# expansionboard.net
KiCad netlist of a schematic drawn in EAGLE
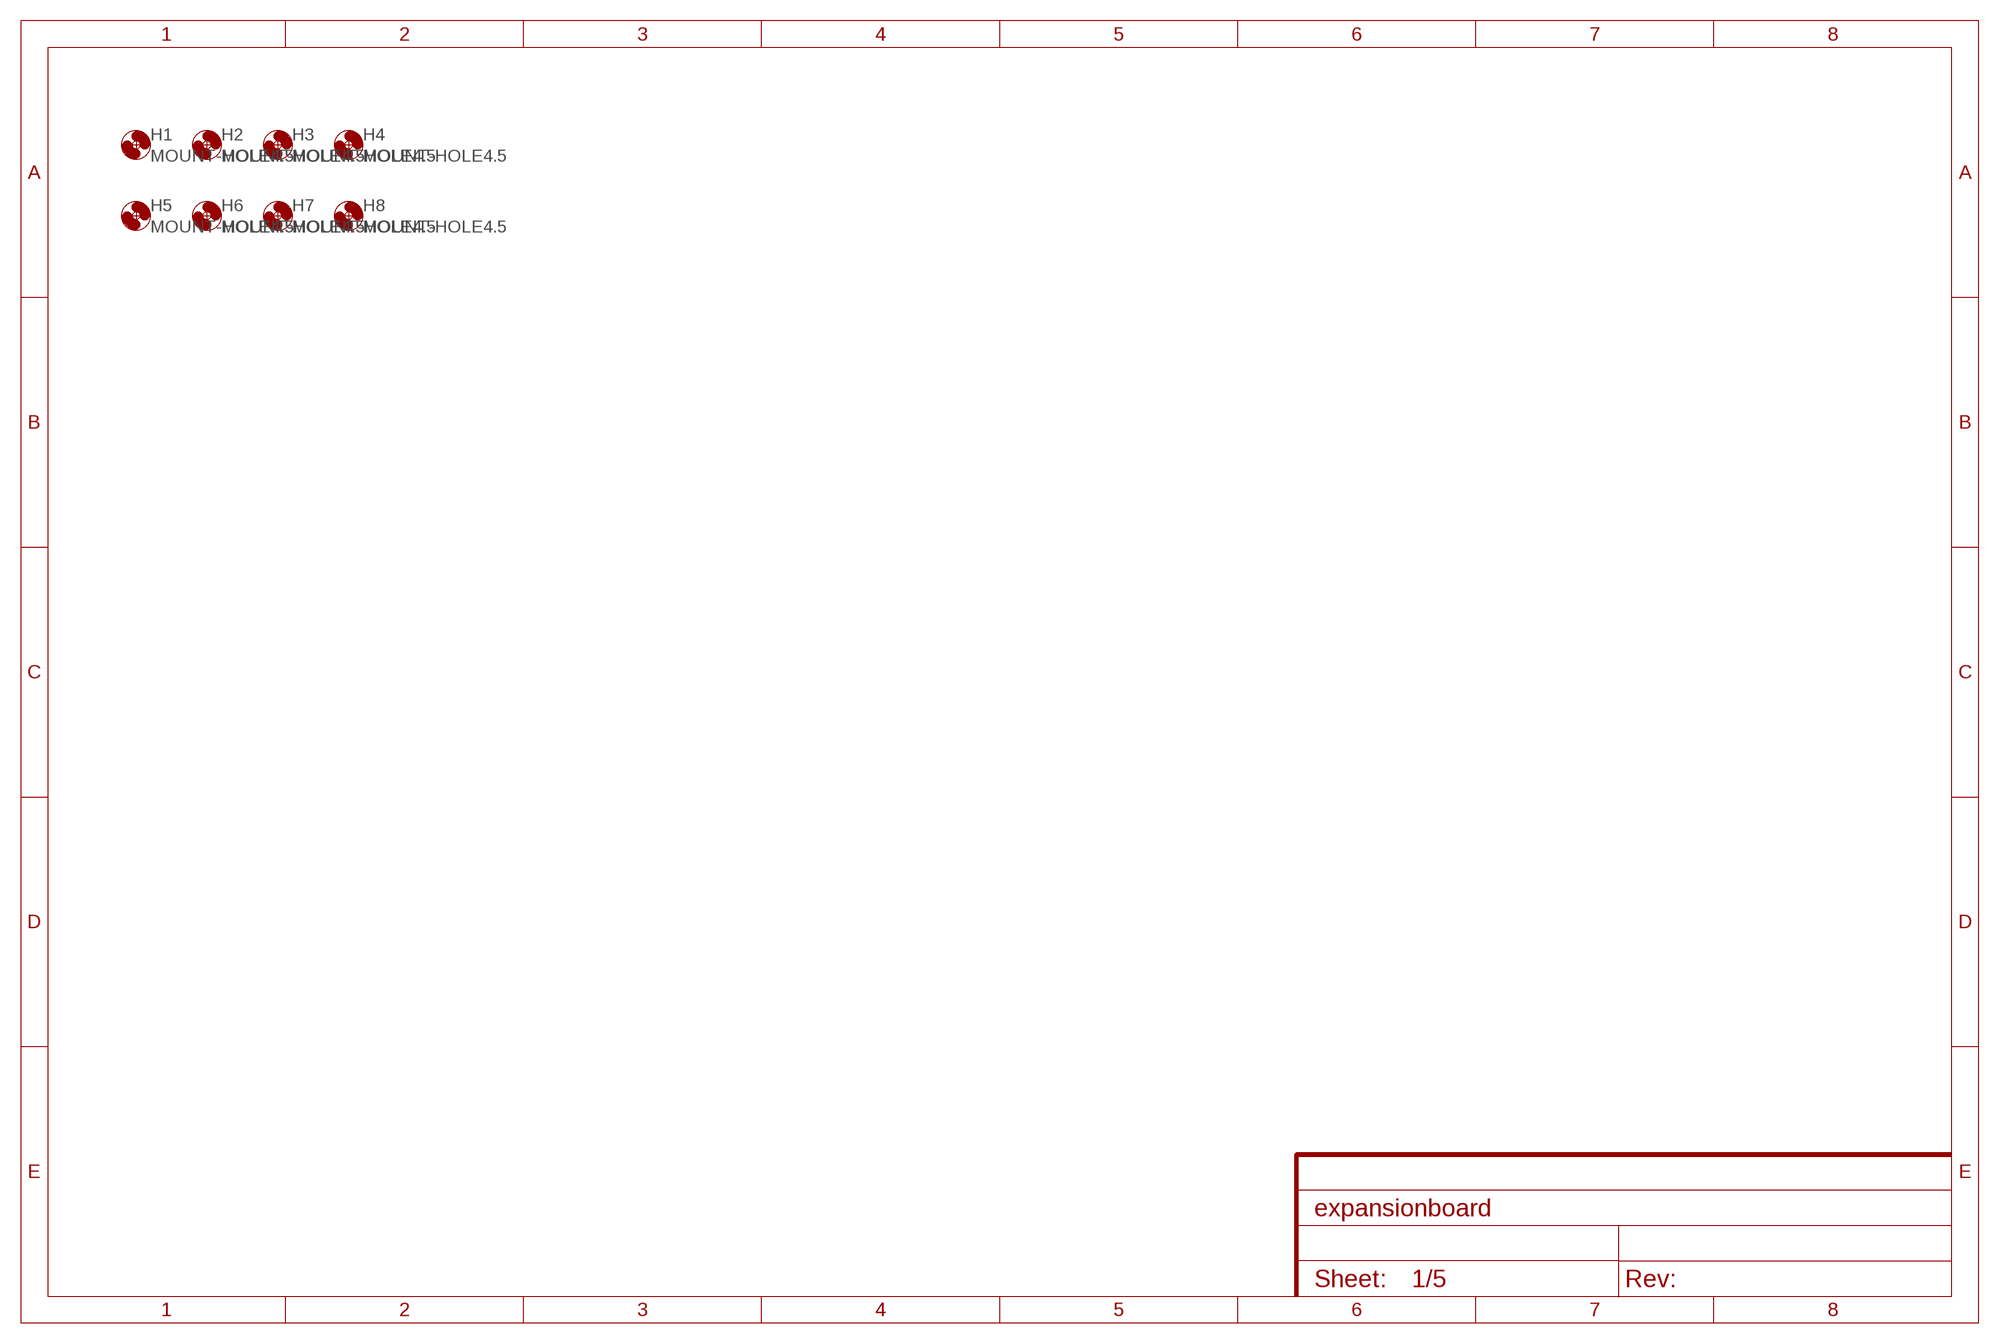
[diagram p0: schematic, sheet 1]
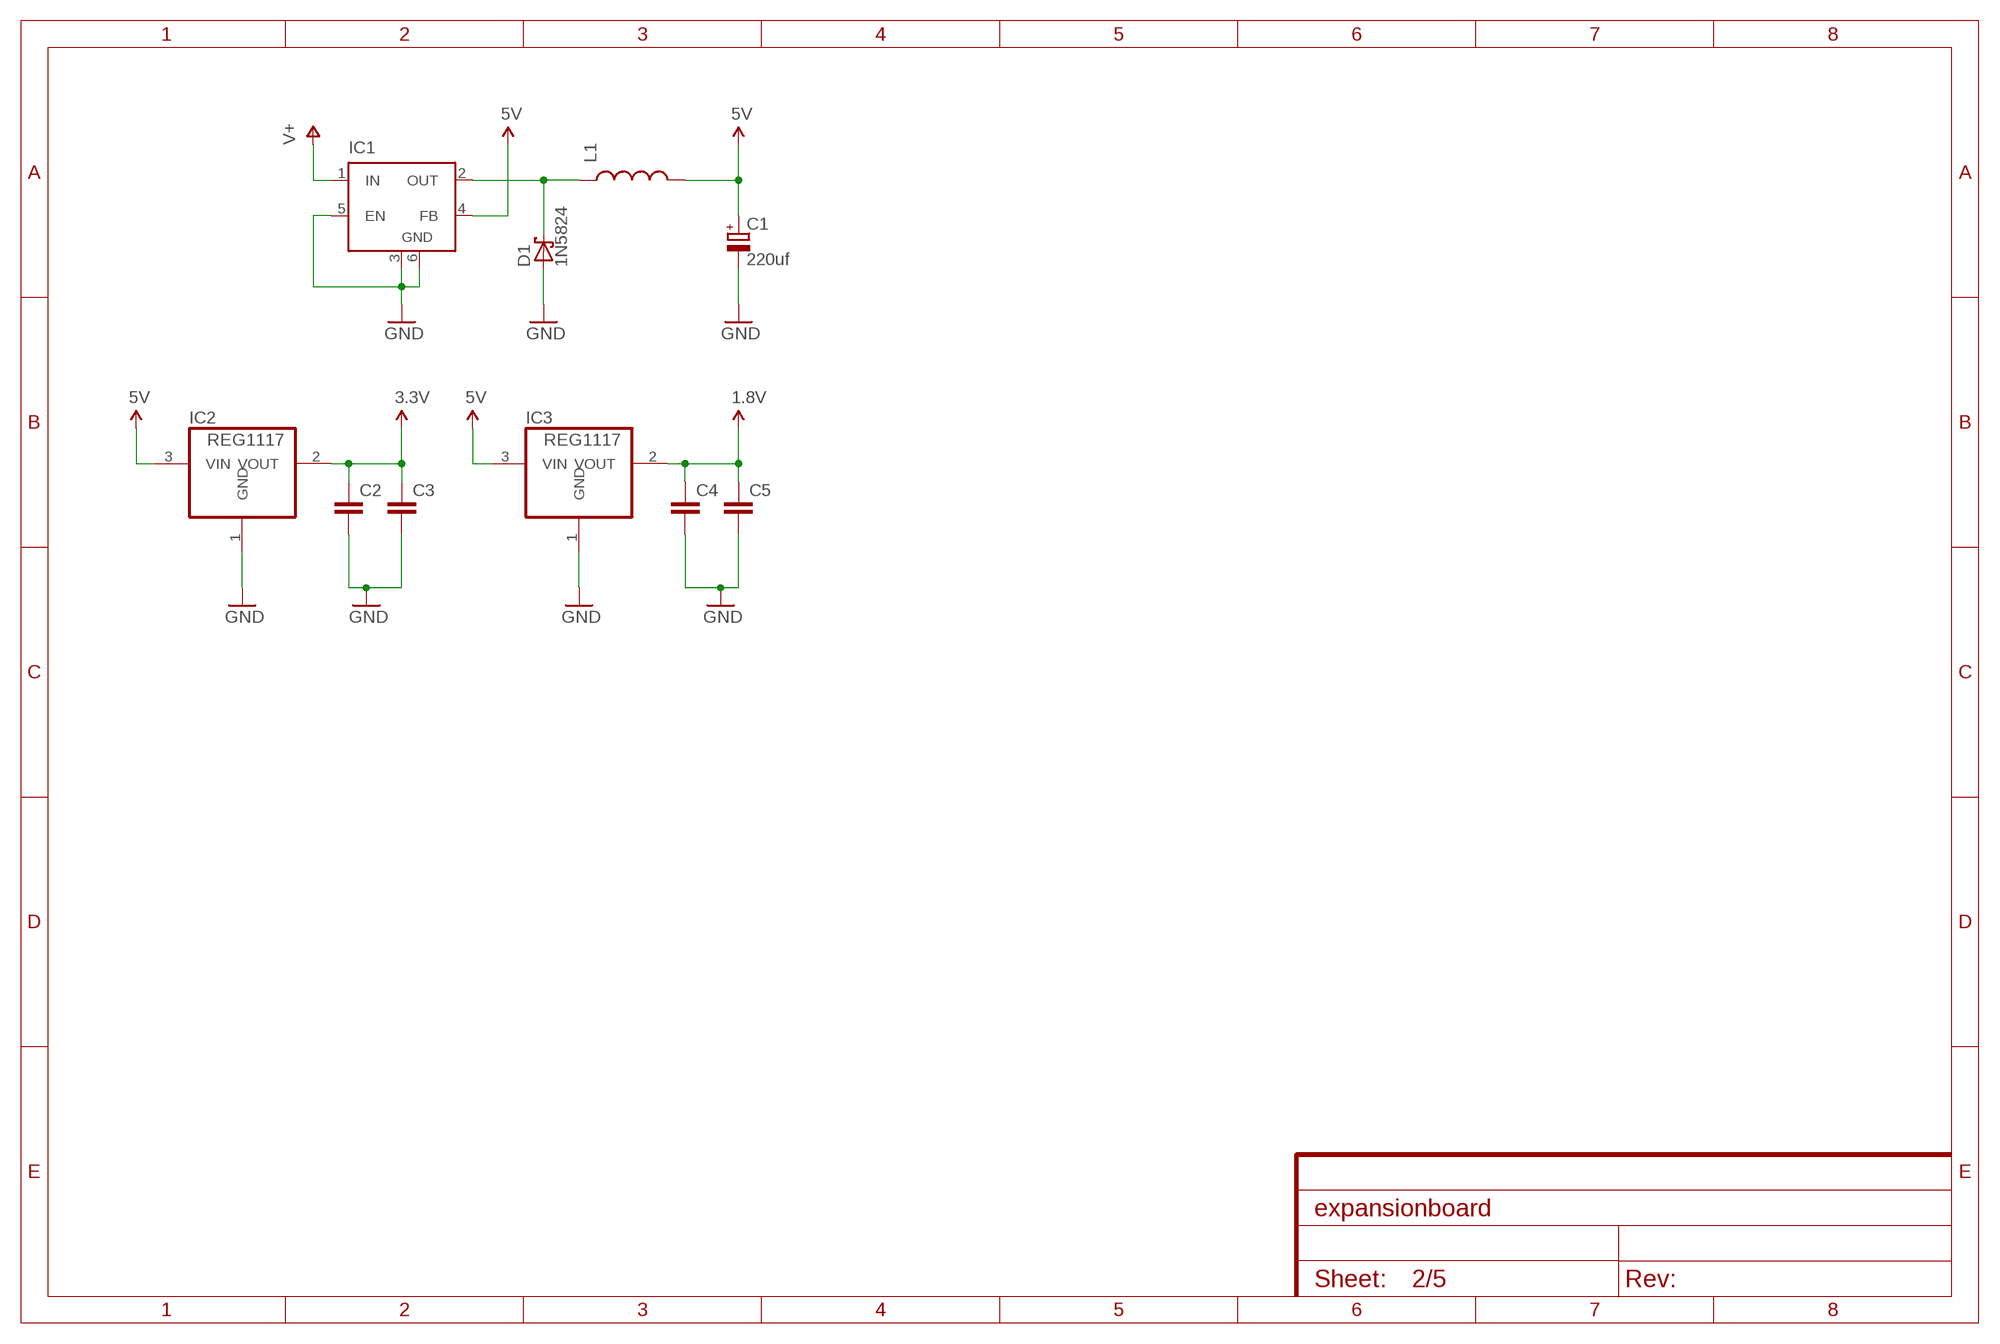
[diagram p1: schematic, sheet 2]
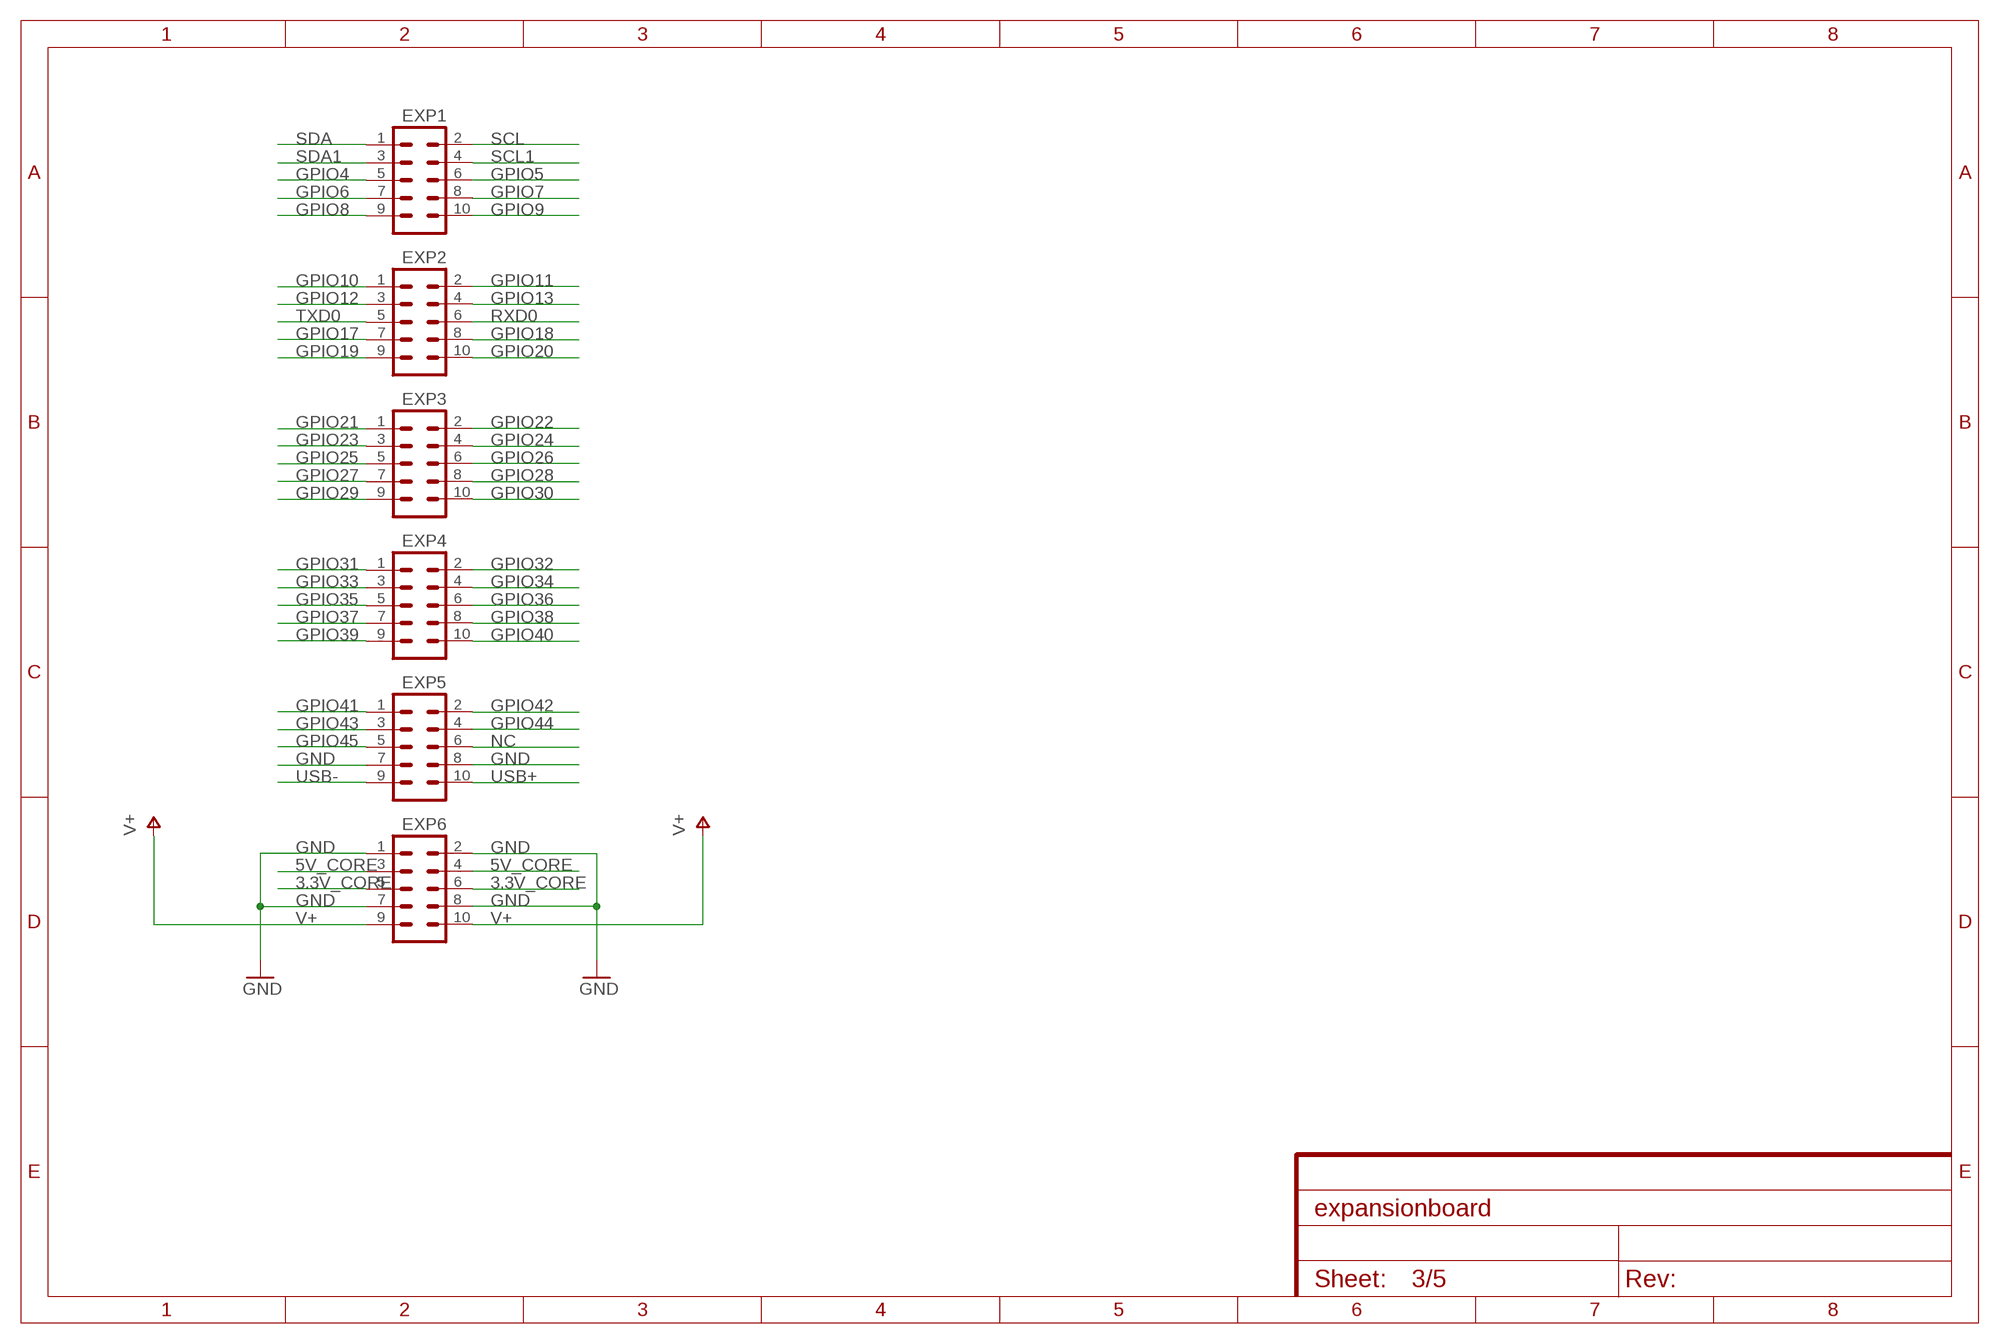
[diagram p2: schematic, sheet 3]
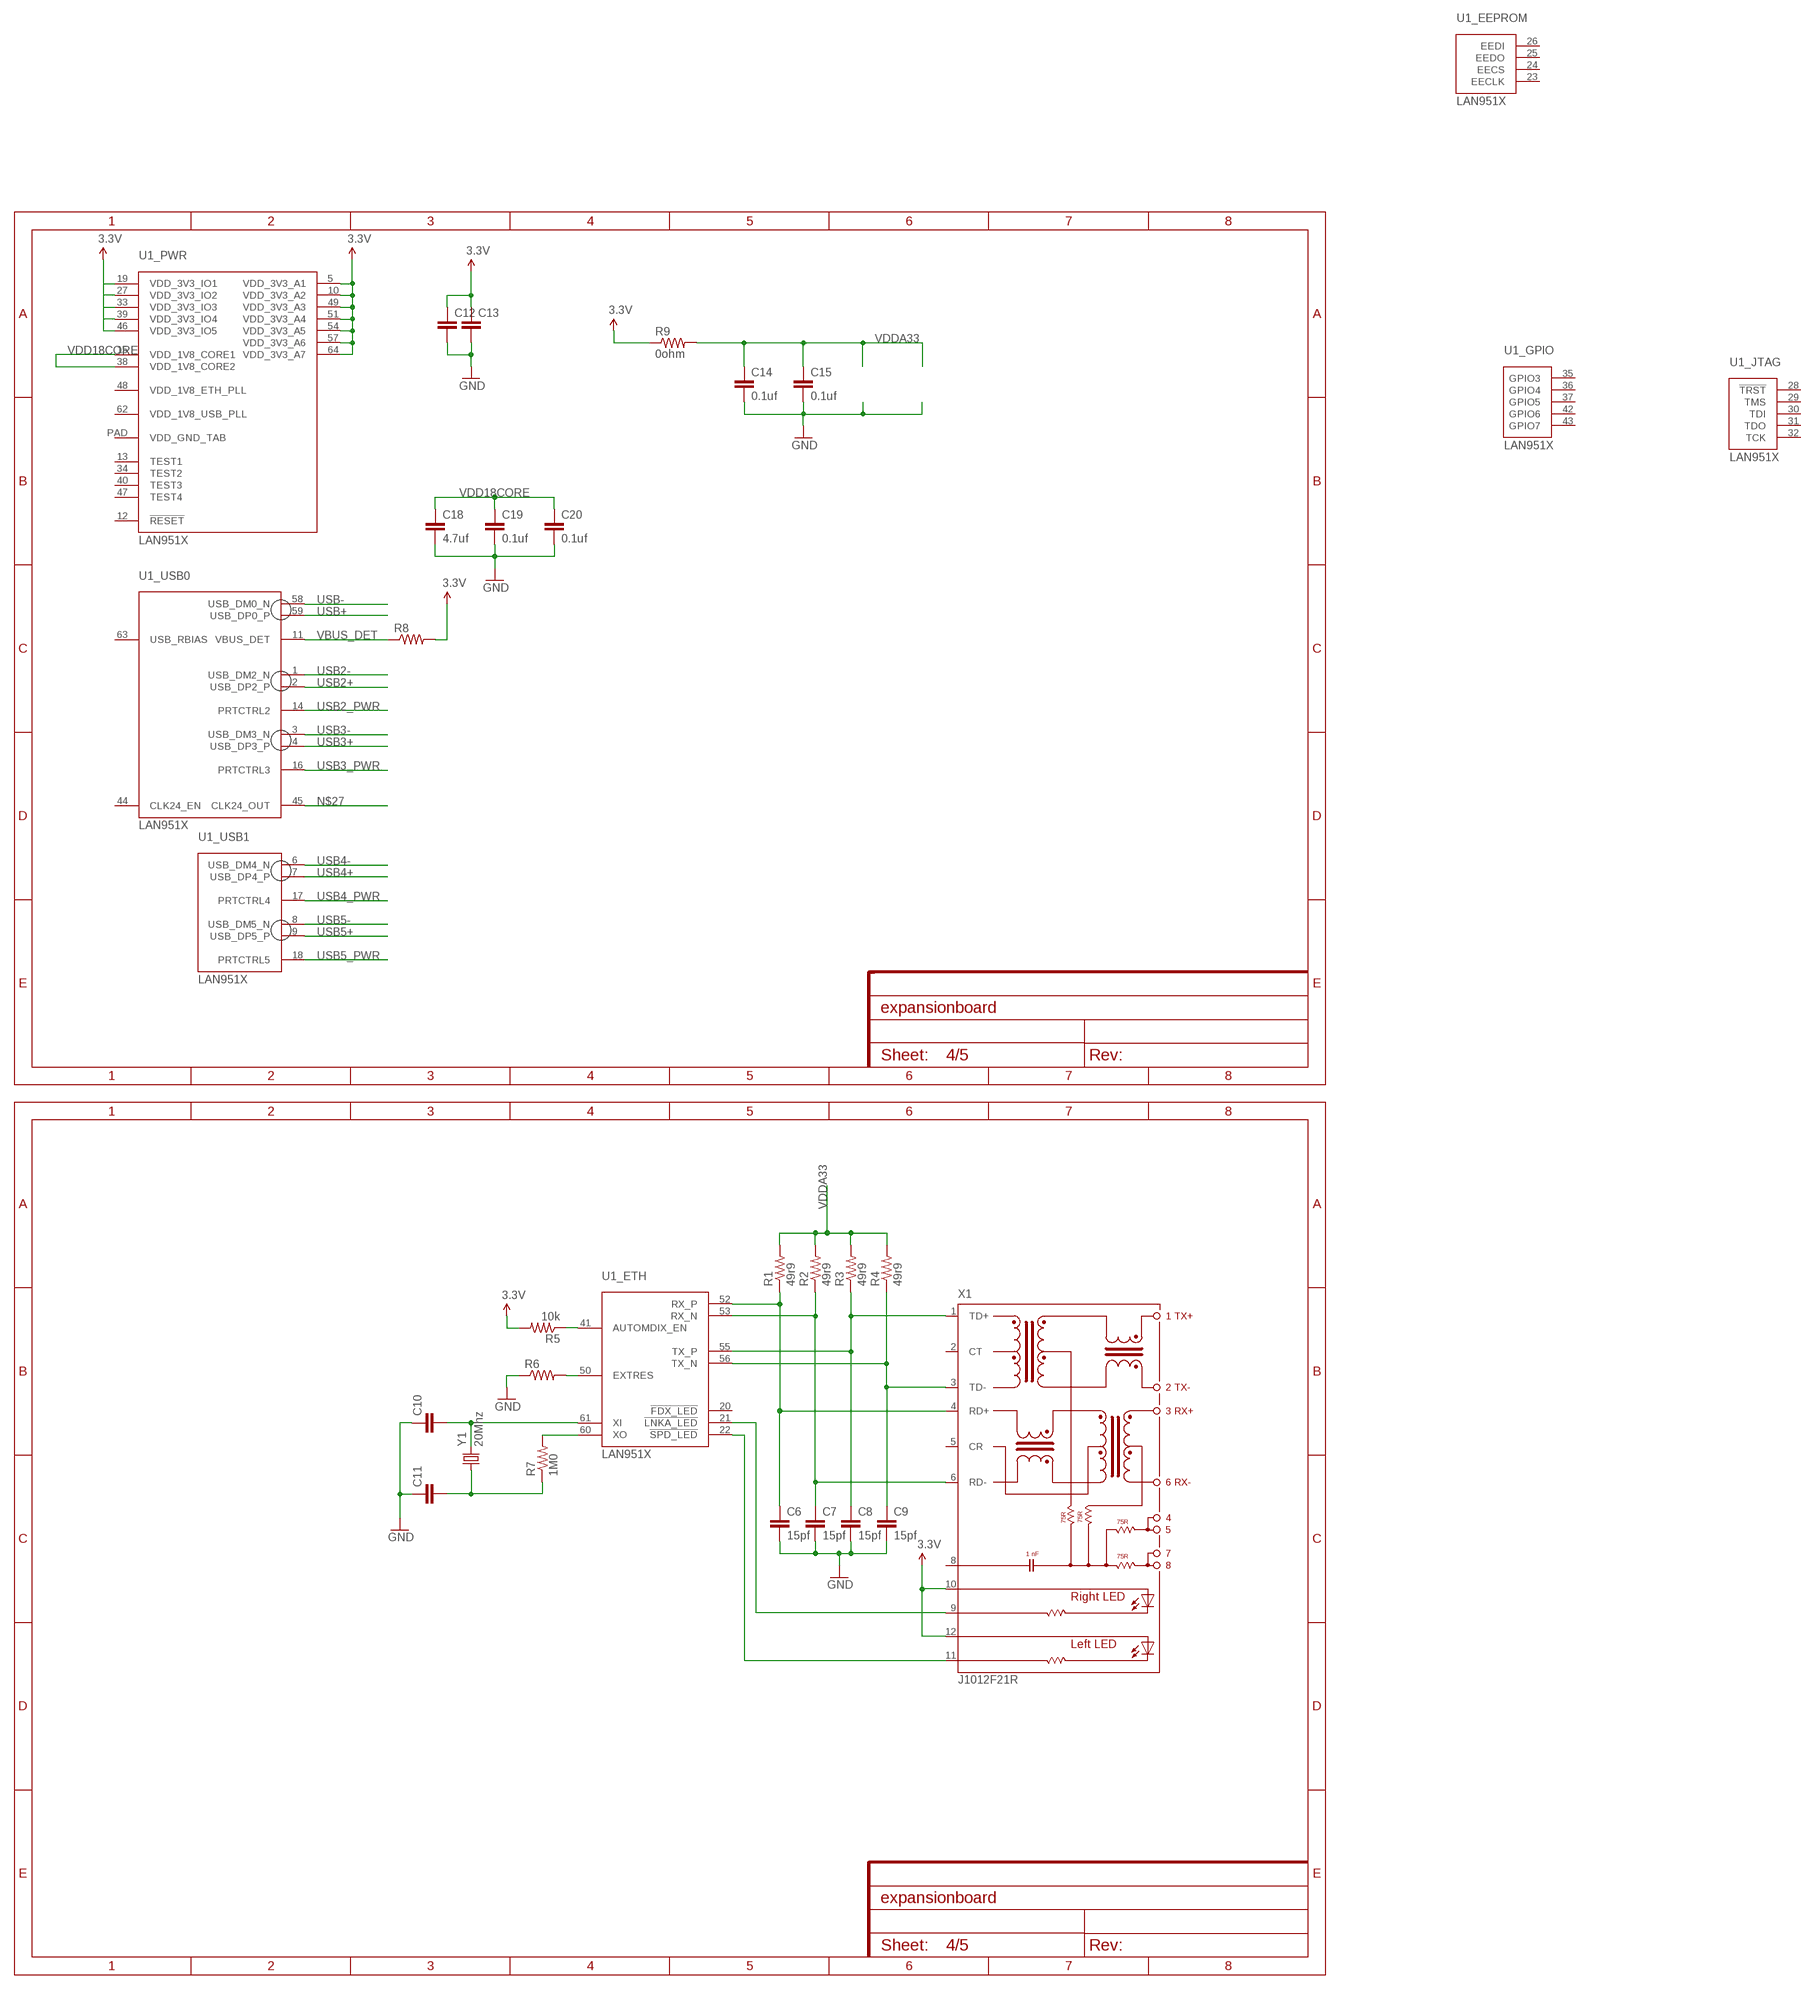
[diagram p3: schematic, sheet 4]
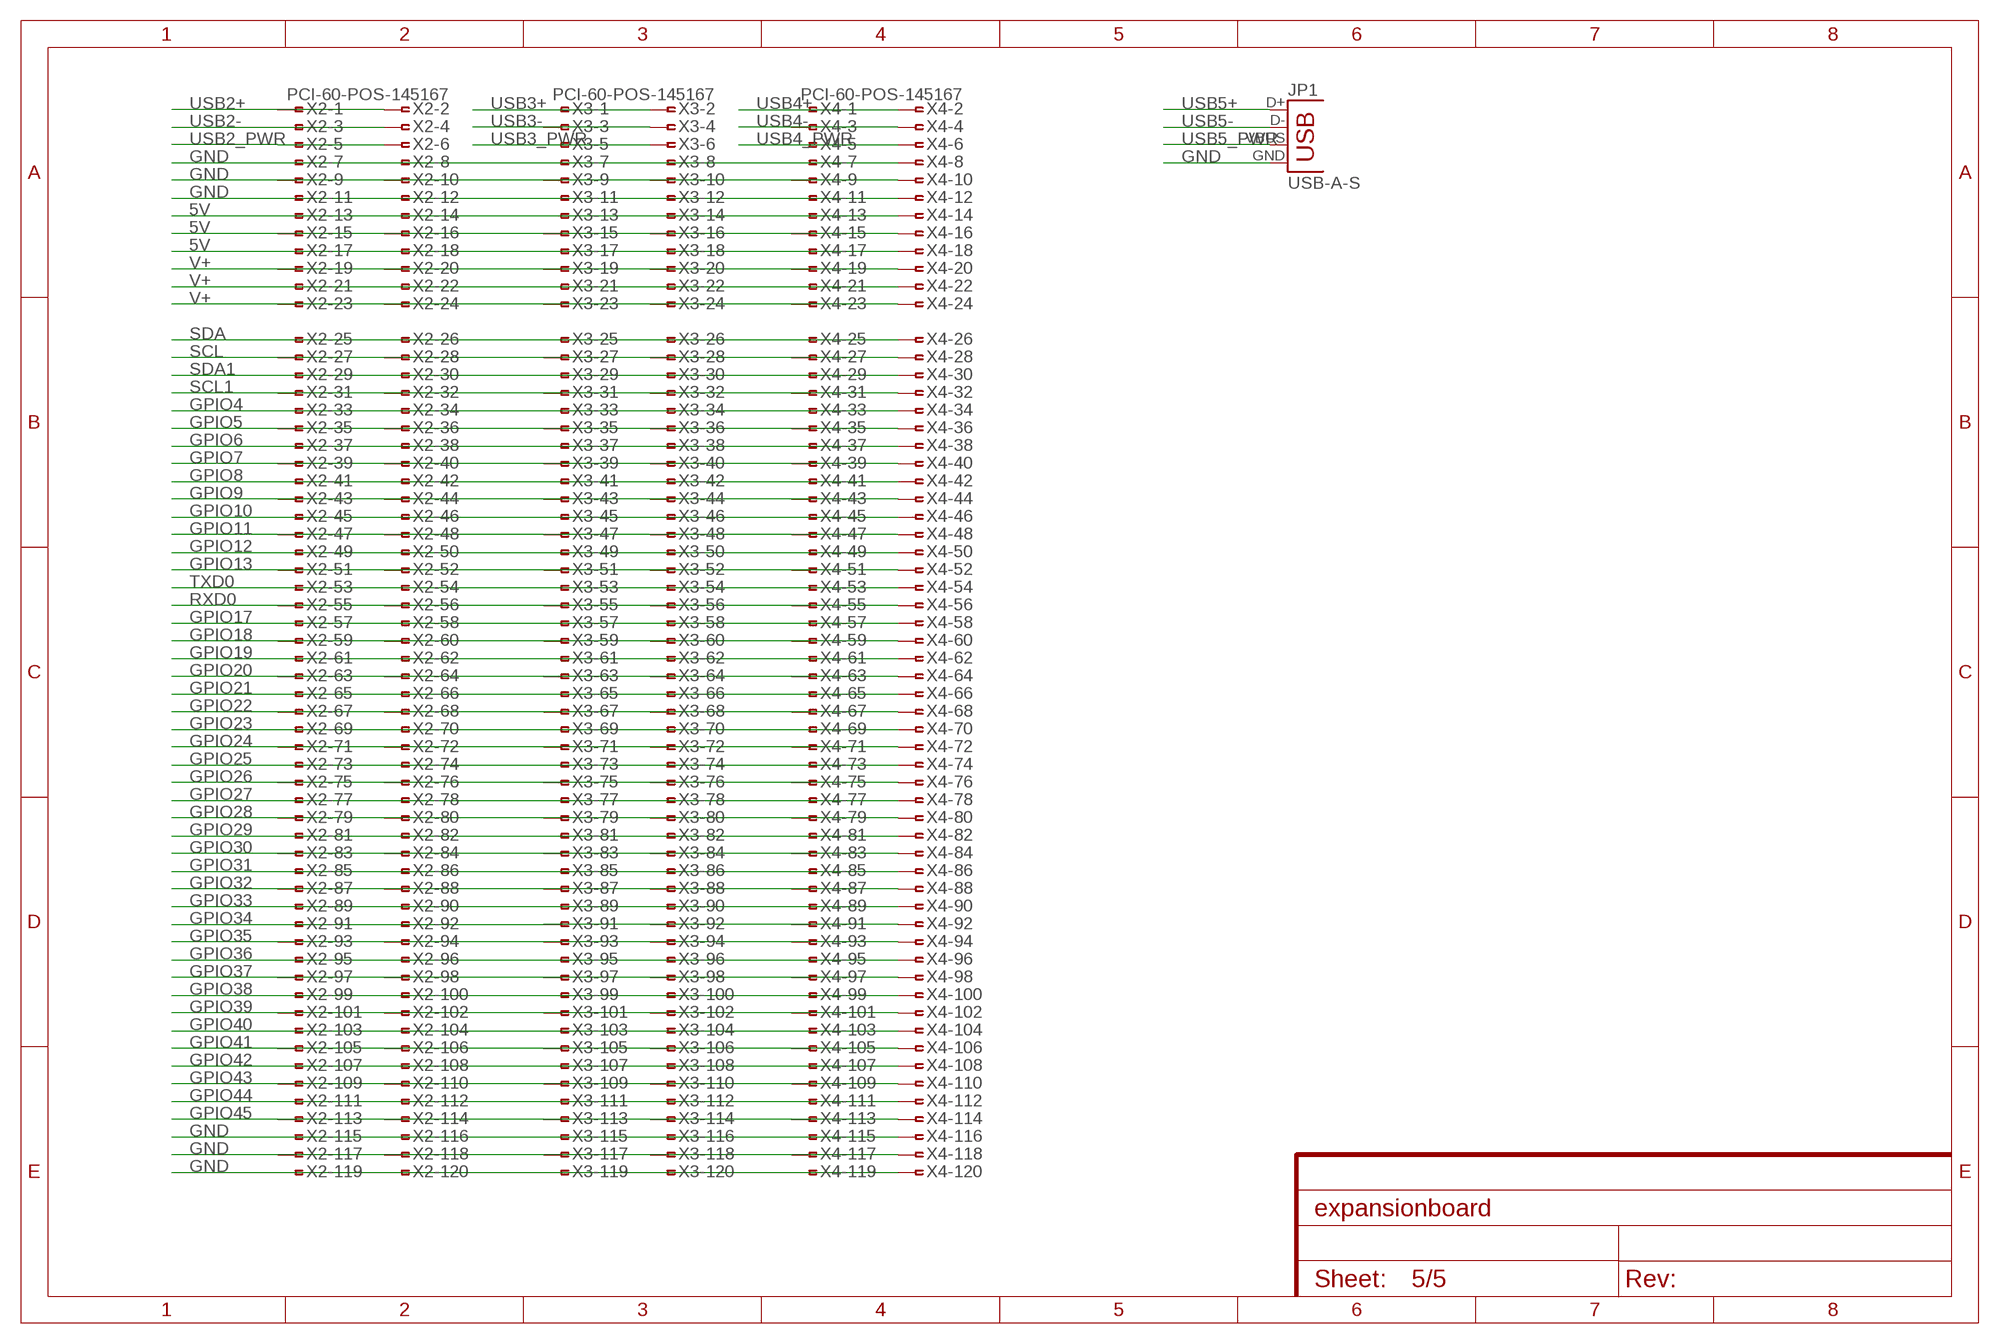
[diagram p4: schematic, sheet 5]

(export (version "E")
  (design (tool "Eeschema 10.0.6"))
  (components
    (comp (ref "C1")
      (value "220uf")
      (footprint "eagle-import:E2,5-6")
      (libsource (lib "eagle-import") (part "CPOL-EUE2.5-6"))
    )
    (comp (ref "C2")
      (value "CAP1206")
      (footprint "eagle-import:1206")
      (libsource (lib "eagle-import") (part "CAP1206"))
    )
    (comp (ref "C3")
      (value "CAP1206")
      (footprint "eagle-import:1206")
      (libsource (lib "eagle-import") (part "CAP1206"))
    )
    (comp (ref "C4")
      (value "CAP1206")
      (footprint "eagle-import:1206")
      (libsource (lib "eagle-import") (part "CAP1206"))
    )
    (comp (ref "C5")
      (value "CAP1206")
      (footprint "eagle-import:1206")
      (libsource (lib "eagle-import") (part "CAP1206"))
    )
    (comp (ref "D1")
      (value "1N5824")
      (footprint "eagle-import:DO41-7.6")
      (libsource (lib "eagle-import") (part "1N5817-B"))
    )
    (comp (ref "IC1")
      (value "LM2596S")
      (footprint "eagle-import:TO263-5")
      (libsource (lib "eagle-import") (part "LM2596S"))
    )
    (comp (ref "IC2")
      (value "REG1117")
      (footprint "eagle-import:SOT223")
      (libsource (lib "eagle-import") (part "REG1117"))
    )
    (comp (ref "IC3")
      (value "REG1117")
      (footprint "eagle-import:SOT223")
      (libsource (lib "eagle-import") (part "REG1117"))
    )
    (comp (ref "L1")
      (value "INDUCTORSRU1038")
      (footprint "eagle-import:SRU1038")
      (libsource (lib "eagle-import") (part "INDUCTORSRU1038"))
    )
    (comp (ref "EXP1")
      (value "M05X2SHD_LOCK")
      (footprint "eagle-import:2X5-SHROUDED_LOCK")
      (libsource (lib "eagle-import") (part "M05X2SHD_LOCK"))
    )
    (comp (ref "EXP2")
      (value "M05X2SHD_LOCK")
      (footprint "eagle-import:2X5-SHROUDED_LOCK")
      (libsource (lib "eagle-import") (part "M05X2SHD_LOCK"))
    )
    (comp (ref "EXP3")
      (value "M05X2SHD_LOCK")
      (footprint "eagle-import:2X5-SHROUDED_LOCK")
      (libsource (lib "eagle-import") (part "M05X2SHD_LOCK"))
    )
    (comp (ref "EXP4")
      (value "M05X2SHD_LOCK")
      (footprint "eagle-import:2X5-SHROUDED_LOCK")
      (libsource (lib "eagle-import") (part "M05X2SHD_LOCK"))
    )
    (comp (ref "EXP5")
      (value "M05X2SHD_LOCK")
      (footprint "eagle-import:2X5-SHROUDED_LOCK")
      (libsource (lib "eagle-import") (part "M05X2SHD_LOCK"))
    )
    (comp (ref "EXP6")
      (value "M05X2SHD_LOCK")
      (footprint "eagle-import:2X5-SHROUDED_LOCK")
      (libsource (lib "eagle-import") (part "M05X2SHD_LOCK"))
    )
    (comp (ref "JP1")
      (value "USB-A-S")
      (footprint "eagle-import:USB-A-S")
      (libsource (lib "eagle-import") (part "USB-A-S"))
    )
    (comp (ref "X2")
      (value "PCI-60-POS-145167")
      (footprint "eagle-import:145167-2")
      (libsource (lib "eagle-import") (part "PCI-60-POS-145167"))
    )
    (comp (ref "X3")
      (value "PCI-60-POS-145167")
      (footprint "eagle-import:145167-2")
      (libsource (lib "eagle-import") (part "PCI-60-POS-145167"))
    )
    (comp (ref "X4")
      (value "PCI-60-POS-145167")
      (footprint "eagle-import:145167-2")
      (libsource (lib "eagle-import") (part "PCI-60-POS-145167"))
    )
    (comp (ref "C6")
      (value "15pf")
      (footprint "eagle-import:CAP-PTH-SMALLEZ")
      (libsource (lib "eagle-import") (part "CAPEZ"))
    )
    (comp (ref "C7")
      (value "15pf")
      (footprint "eagle-import:CAP-PTH-SMALLEZ")
      (libsource (lib "eagle-import") (part "CAPEZ"))
    )
    (comp (ref "C8")
      (value "15pf")
      (footprint "eagle-import:CAP-PTH-SMALLEZ")
      (libsource (lib "eagle-import") (part "CAPEZ"))
    )
    (comp (ref "C9")
      (value "15pf")
      (footprint "eagle-import:CAP-PTH-SMALLEZ")
      (libsource (lib "eagle-import") (part "CAPEZ"))
    )
    (comp (ref "C10")
      (value "CAPEZ")
      (footprint "eagle-import:CAP-PTH-SMALLEZ")
      (libsource (lib "eagle-import") (part "CAPEZ"))
    )
    (comp (ref "C11")
      (value "CAPEZ")
      (footprint "eagle-import:CAP-PTH-SMALLEZ")
      (libsource (lib "eagle-import") (part "CAPEZ"))
    )
    (comp (ref "C12")
      (value "CAPEZ")
      (footprint "eagle-import:CAP-PTH-SMALLEZ")
      (libsource (lib "eagle-import") (part "CAPEZ"))
    )
    (comp (ref "C13")
      (value "CAPEZ")
      (footprint "eagle-import:CAP-PTH-SMALLEZ")
      (libsource (lib "eagle-import") (part "CAPEZ"))
    )
    (comp (ref "C14")
      (value "0.1uf")
      (footprint "eagle-import:1206")
      (libsource (lib "eagle-import") (part "CAP1206"))
    )
    (comp (ref "C15")
      (value "0.1uf")
      (footprint "eagle-import:1206")
      (libsource (lib "eagle-import") (part "CAP1206"))
    )
    (comp (ref "C18")
      (value "4.7uf")
      (footprint "eagle-import:1206")
      (libsource (lib "eagle-import") (part "CAP1206"))
    )
    (comp (ref "C19")
      (value "0.1uf")
      (footprint "eagle-import:1206")
      (libsource (lib "eagle-import") (part "CAP1206"))
    )
    (comp (ref "C20")
      (value "0.1uf")
      (footprint "eagle-import:1206")
      (libsource (lib "eagle-import") (part "CAP1206"))
    )
    (comp (ref "R1")
      (value "49r9")
      (footprint "eagle-import:AXIAL-0.3EZ")
      (libsource (lib "eagle-import") (part "RESISTOREZ"))
    )
    (comp (ref "R2")
      (value "49r9")
      (footprint "eagle-import:AXIAL-0.3EZ")
      (libsource (lib "eagle-import") (part "RESISTOREZ"))
    )
    (comp (ref "R3")
      (value "49r9")
      (footprint "eagle-import:AXIAL-0.3EZ")
      (libsource (lib "eagle-import") (part "RESISTOREZ"))
    )
    (comp (ref "R4")
      (value "49r9")
      (footprint "eagle-import:AXIAL-0.3EZ")
      (libsource (lib "eagle-import") (part "RESISTOREZ"))
    )
    (comp (ref "R5")
      (value "10k")
      (footprint "eagle-import:AXIAL-0.3EZ")
      (libsource (lib "eagle-import") (part "RESISTOREZ"))
    )
    (comp (ref "R6")
      (value "RESISTOREZ")
      (footprint "eagle-import:AXIAL-0.3EZ")
      (libsource (lib "eagle-import") (part "RESISTOREZ"))
    )
    (comp (ref "R7")
      (value "1M0")
      (footprint "eagle-import:AXIAL-0.3EZ")
      (libsource (lib "eagle-import") (part "RESISTOREZ"))
    )
    (comp (ref "R8")
      (value "RESISTOR1206")
      (footprint "eagle-import:1206")
      (libsource (lib "eagle-import") (part "RESISTOR1206"))
    )
    (comp (ref "R9")
      (value "0ohm")
      (footprint "eagle-import:1206")
      (libsource (lib "eagle-import") (part "RESISTOR1206"))
    )
    (comp (ref "U1")
      (value "LAN951X")
      (footprint "eagle-import:QFN-64")
      (libsource (lib "eagle-import") (part "LAN951X"))
    )
    (comp (ref "X1")
      (value "J1012F21R")
      (footprint "eagle-import:J1")
      (libsource (lib "eagle-import") (part "J1012F21R"))
    )
    (comp (ref "Y1")
      (value "20Mhz")
      (footprint "eagle-import:HC49US")
      (libsource (lib "eagle-import") (part "CRYSTALHC49US"))
    )
    (comp (ref "H1")
      (value "MOUNT-HOLE4.5")
      (footprint "eagle-import:4,5")
      (libsource (lib "eagle-import") (part "MOUNT-HOLE4.5"))
    )
    (comp (ref "H2")
      (value "MOUNT-HOLE4.5")
      (footprint "eagle-import:4,5")
      (libsource (lib "eagle-import") (part "MOUNT-HOLE4.5"))
    )
    (comp (ref "H3")
      (value "MOUNT-HOLE4.5")
      (footprint "eagle-import:4,5")
      (libsource (lib "eagle-import") (part "MOUNT-HOLE4.5"))
    )
    (comp (ref "H4")
      (value "MOUNT-HOLE4.5")
      (footprint "eagle-import:4,5")
      (libsource (lib "eagle-import") (part "MOUNT-HOLE4.5"))
    )
    (comp (ref "H5")
      (value "MOUNT-HOLE4.5")
      (footprint "eagle-import:4,5")
      (libsource (lib "eagle-import") (part "MOUNT-HOLE4.5"))
    )
    (comp (ref "H6")
      (value "MOUNT-HOLE4.5")
      (footprint "eagle-import:4,5")
      (libsource (lib "eagle-import") (part "MOUNT-HOLE4.5"))
    )
    (comp (ref "H7")
      (value "MOUNT-HOLE4.5")
      (footprint "eagle-import:4,5")
      (libsource (lib "eagle-import") (part "MOUNT-HOLE4.5"))
    )
    (comp (ref "H8")
      (value "MOUNT-HOLE4.5")
      (footprint "eagle-import:4,5")
      (libsource (lib "eagle-import") (part "MOUNT-HOLE4.5"))
    )
  )
  (nets
    (net (code "1") (name "1.8V") (class "Default")
      (node (ref "C4") (pin "1") (pinfunction "1_1") (pintype "passive"))
      (node (ref "C5") (pin "1") (pinfunction "1_1") (pintype "passive"))
      (node (ref "IC3") (pin "2") (pinfunction "VOUT_2") (pintype "output"))
    )
    (net (code "2") (name "3.3V") (class "Default")
      (node (ref "C12") (pin "1") (pinfunction "1_1") (pintype "passive"))
      (node (ref "C13") (pin "1") (pinfunction "1_1") (pintype "passive"))
      (node (ref "C2") (pin "1") (pinfunction "1_1") (pintype "passive"))
      (node (ref "C3") (pin "1") (pinfunction "1_1") (pintype "passive"))
      (node (ref "IC2") (pin "2") (pinfunction "VOUT_2") (pintype "output"))
      (node (ref "R5") (pin "P$2") (pinfunction "2_P$2") (pintype "passive"))
      (node (ref "R8") (pin "2") (pinfunction "2_2") (pintype "passive"))
      (node (ref "R9") (pin "1") (pinfunction "1_1") (pintype "passive"))
      (node (ref "U1") (pin "10") (pinfunction "VDD_3V3_A2_10") (pintype "bidirectional"))
      (node (ref "U1") (pin "19") (pinfunction "VDD_3V3_IO1_19") (pintype "bidirectional"))
      (node (ref "U1") (pin "27") (pinfunction "VDD_3V3_IO2_27") (pintype "bidirectional"))
      (node (ref "U1") (pin "33") (pinfunction "VDD_3V3_IO3_33") (pintype "bidirectional"))
      (node (ref "U1") (pin "39") (pinfunction "VDD_3V3_IO4_39") (pintype "bidirectional"))
      (node (ref "U1") (pin "46") (pinfunction "VDD_3V3_IO5_46") (pintype "bidirectional"))
      (node (ref "U1") (pin "49") (pinfunction "VDD_3V3_A3_49") (pintype "bidirectional"))
      (node (ref "U1") (pin "5") (pinfunction "VDD_3V3_A1_5") (pintype "bidirectional"))
      (node (ref "U1") (pin "51") (pinfunction "VDD_3V3_A4_51") (pintype "bidirectional"))
      (node (ref "U1") (pin "54") (pinfunction "VDD_3V3_A5_54") (pintype "bidirectional"))
      (node (ref "U1") (pin "57") (pinfunction "VDD_3V3_A6_57") (pintype "bidirectional"))
      (node (ref "U1") (pin "64") (pinfunction "VDD_3V3_A7_64") (pintype "bidirectional"))
      (node (ref "X1") (pin "10") (pinfunction "A-R_10") (pintype "passive"))
      (node (ref "X1") (pin "12") (pinfunction "A-L_12") (pintype "passive"))
    )
    (net (code "3") (name "3.3V_CORE") (class "Default")
      (node (ref "EXP6") (pin "5") (pinfunction "5_5") (pintype "passive"))
      (node (ref "EXP6") (pin "6") (pinfunction "6_6") (pintype "passive"))
    )
    (net (code "4") (name "5V") (class "Default")
      (node (ref "C1") (pin "+") (pinfunction "+_+") (pintype "passive"))
      (node (ref "IC1") (pin "4") (pinfunction "FB_4") (pintype "input"))
      (node (ref "IC2") (pin "3") (pinfunction "VIN_3") (pintype "input"))
      (node (ref "IC3") (pin "3") (pinfunction "VIN_3") (pintype "input"))
      (node (ref "L1") (pin "2") (pinfunction "2_2") (pintype "passive"))
      (node (ref "X2") (pin "13") (pinfunction "1_13") (pintype "passive"))
      (node (ref "X2") (pin "14") (pinfunction "1_14") (pintype "passive"))
      (node (ref "X2") (pin "15") (pinfunction "1_15") (pintype "passive"))
      (node (ref "X2") (pin "16") (pinfunction "1_16") (pintype "passive"))
      (node (ref "X2") (pin "17") (pinfunction "1_17") (pintype "passive"))
      (node (ref "X2") (pin "18") (pinfunction "1_18") (pintype "passive"))
      (node (ref "X3") (pin "13") (pinfunction "1_13") (pintype "passive"))
      (node (ref "X3") (pin "14") (pinfunction "1_14") (pintype "passive"))
      (node (ref "X3") (pin "15") (pinfunction "1_15") (pintype "passive"))
      (node (ref "X3") (pin "16") (pinfunction "1_16") (pintype "passive"))
      (node (ref "X3") (pin "17") (pinfunction "1_17") (pintype "passive"))
      (node (ref "X3") (pin "18") (pinfunction "1_18") (pintype "passive"))
      (node (ref "X4") (pin "13") (pinfunction "1_13") (pintype "passive"))
      (node (ref "X4") (pin "14") (pinfunction "1_14") (pintype "passive"))
      (node (ref "X4") (pin "15") (pinfunction "1_15") (pintype "passive"))
      (node (ref "X4") (pin "16") (pinfunction "1_16") (pintype "passive"))
      (node (ref "X4") (pin "17") (pinfunction "1_17") (pintype "passive"))
      (node (ref "X4") (pin "18") (pinfunction "1_18") (pintype "passive"))
    )
    (net (code "5") (name "5V_CORE") (class "Default")
      (node (ref "EXP6") (pin "3") (pinfunction "3_3") (pintype "passive"))
      (node (ref "EXP6") (pin "4") (pinfunction "4_4") (pintype "passive"))
    )
    (net (code "6") (name "GND") (class "Default")
      (node (ref "C1") (pin "-") (pinfunction "-_-") (pintype "passive"))
      (node (ref "C10") (pin "1") (pinfunction "1_1") (pintype "passive"))
      (node (ref "C11") (pin "1") (pinfunction "1_1") (pintype "passive"))
      (node (ref "C12") (pin "2") (pinfunction "2_2") (pintype "passive"))
      (node (ref "C13") (pin "2") (pinfunction "2_2") (pintype "passive"))
      (node (ref "C14") (pin "2") (pinfunction "2_2") (pintype "passive"))
      (node (ref "C15") (pin "2") (pinfunction "2_2") (pintype "passive"))
      (node (ref "C18") (pin "2") (pinfunction "2_2") (pintype "passive"))
      (node (ref "C19") (pin "2") (pinfunction "2_2") (pintype "passive"))
      (node (ref "C2") (pin "2") (pinfunction "2_2") (pintype "passive"))
      (node (ref "C20") (pin "2") (pinfunction "2_2") (pintype "passive"))
      (node (ref "C3") (pin "2") (pinfunction "2_2") (pintype "passive"))
      (node (ref "C4") (pin "2") (pinfunction "2_2") (pintype "passive"))
      (node (ref "C5") (pin "2") (pinfunction "2_2") (pintype "passive"))
      (node (ref "C6") (pin "2") (pinfunction "2_2") (pintype "passive"))
      (node (ref "C7") (pin "2") (pinfunction "2_2") (pintype "passive"))
      (node (ref "C8") (pin "2") (pinfunction "2_2") (pintype "passive"))
      (node (ref "C9") (pin "2") (pinfunction "2_2") (pintype "passive"))
      (node (ref "D1") (pin "A") (pinfunction "A_A") (pintype "passive"))
      (node (ref "EXP5") (pin "7") (pinfunction "7_7") (pintype "passive"))
      (node (ref "EXP5") (pin "8") (pinfunction "8_8") (pintype "passive"))
      (node (ref "EXP6") (pin "1") (pinfunction "1_1") (pintype "passive"))
      (node (ref "EXP6") (pin "2") (pinfunction "2_2") (pintype "passive"))
      (node (ref "EXP6") (pin "7") (pinfunction "7_7") (pintype "passive"))
      (node (ref "EXP6") (pin "8") (pinfunction "8_8") (pintype "passive"))
      (node (ref "IC1") (pin "3") (pinfunction "GND_3") (pintype "power_in"))
      (node (ref "IC1") (pin "5") (pinfunction "EN_5") (pintype "input"))
      (node (ref "IC1") (pin "6") (pinfunction "GND_6") (pintype "power_in"))
      (node (ref "IC2") (pin "1") (pinfunction "GND_1") (pintype "power_in"))
      (node (ref "IC3") (pin "1") (pinfunction "GND_1") (pintype "power_in"))
      (node (ref "JP1") (pin "GND") (pinfunction "GND_GND") (pintype "bidirectional"))
      (node (ref "R6") (pin "P$1") (pinfunction "1_P$1") (pintype "passive"))
      (node (ref "X2") (pin "10") (pinfunction "1_10") (pintype "passive"))
      (node (ref "X2") (pin "11") (pinfunction "1_11") (pintype "passive"))
      (node (ref "X2") (pin "115") (pinfunction "1_115") (pintype "passive"))
      (node (ref "X2") (pin "116") (pinfunction "1_116") (pintype "passive"))
      (node (ref "X2") (pin "117") (pinfunction "1_117") (pintype "passive"))
      (node (ref "X2") (pin "118") (pinfunction "1_118") (pintype "passive"))
      (node (ref "X2") (pin "119") (pinfunction "1_119") (pintype "passive"))
      (node (ref "X2") (pin "12") (pinfunction "1_12") (pintype "passive"))
      (node (ref "X2") (pin "120") (pinfunction "1_120") (pintype "passive"))
      (node (ref "X2") (pin "7") (pinfunction "1_7") (pintype "passive"))
      (node (ref "X2") (pin "8") (pinfunction "1_8") (pintype "passive"))
      (node (ref "X2") (pin "9") (pinfunction "1_9") (pintype "passive"))
      (node (ref "X3") (pin "10") (pinfunction "1_10") (pintype "passive"))
      (node (ref "X3") (pin "11") (pinfunction "1_11") (pintype "passive"))
      (node (ref "X3") (pin "115") (pinfunction "1_115") (pintype "passive"))
      (node (ref "X3") (pin "116") (pinfunction "1_116") (pintype "passive"))
      (node (ref "X3") (pin "117") (pinfunction "1_117") (pintype "passive"))
      (node (ref "X3") (pin "118") (pinfunction "1_118") (pintype "passive"))
      (node (ref "X3") (pin "119") (pinfunction "1_119") (pintype "passive"))
      (node (ref "X3") (pin "12") (pinfunction "1_12") (pintype "passive"))
      (node (ref "X3") (pin "120") (pinfunction "1_120") (pintype "passive"))
      (node (ref "X3") (pin "7") (pinfunction "1_7") (pintype "passive"))
      (node (ref "X3") (pin "8") (pinfunction "1_8") (pintype "passive"))
      (node (ref "X3") (pin "9") (pinfunction "1_9") (pintype "passive"))
      (node (ref "X4") (pin "10") (pinfunction "1_10") (pintype "passive"))
      (node (ref "X4") (pin "11") (pinfunction "1_11") (pintype "passive"))
      (node (ref "X4") (pin "115") (pinfunction "1_115") (pintype "passive"))
      (node (ref "X4") (pin "116") (pinfunction "1_116") (pintype "passive"))
      (node (ref "X4") (pin "117") (pinfunction "1_117") (pintype "passive"))
      (node (ref "X4") (pin "118") (pinfunction "1_118") (pintype "passive"))
      (node (ref "X4") (pin "119") (pinfunction "1_119") (pintype "passive"))
      (node (ref "X4") (pin "12") (pinfunction "1_12") (pintype "passive"))
      (node (ref "X4") (pin "120") (pinfunction "1_120") (pintype "passive"))
      (node (ref "X4") (pin "7") (pinfunction "1_7") (pintype "passive"))
      (node (ref "X4") (pin "8") (pinfunction "1_8") (pintype "passive"))
      (node (ref "X4") (pin "9") (pinfunction "1_9") (pintype "passive"))
    )
    (net (code "7") (name "GPIO4") (class "Default")
      (node (ref "EXP1") (pin "5") (pinfunction "5_5") (pintype "passive"))
      (node (ref "X2") (pin "33") (pinfunction "1_33") (pintype "passive"))
      (node (ref "X2") (pin "34") (pinfunction "1_34") (pintype "passive"))
      (node (ref "X3") (pin "33") (pinfunction "1_33") (pintype "passive"))
      (node (ref "X3") (pin "34") (pinfunction "1_34") (pintype "passive"))
      (node (ref "X4") (pin "33") (pinfunction "1_33") (pintype "passive"))
      (node (ref "X4") (pin "34") (pinfunction "1_34") (pintype "passive"))
    )
    (net (code "8") (name "GPIO5") (class "Default")
      (node (ref "EXP1") (pin "6") (pinfunction "6_6") (pintype "passive"))
      (node (ref "X2") (pin "35") (pinfunction "1_35") (pintype "passive"))
      (node (ref "X2") (pin "36") (pinfunction "1_36") (pintype "passive"))
      (node (ref "X3") (pin "35") (pinfunction "1_35") (pintype "passive"))
      (node (ref "X3") (pin "36") (pinfunction "1_36") (pintype "passive"))
      (node (ref "X4") (pin "35") (pinfunction "1_35") (pintype "passive"))
      (node (ref "X4") (pin "36") (pinfunction "1_36") (pintype "passive"))
    )
    (net (code "9") (name "GPIO6") (class "Default")
      (node (ref "EXP1") (pin "7") (pinfunction "7_7") (pintype "passive"))
      (node (ref "X2") (pin "37") (pinfunction "1_37") (pintype "passive"))
      (node (ref "X2") (pin "38") (pinfunction "1_38") (pintype "passive"))
      (node (ref "X3") (pin "37") (pinfunction "1_37") (pintype "passive"))
      (node (ref "X3") (pin "38") (pinfunction "1_38") (pintype "passive"))
      (node (ref "X4") (pin "37") (pinfunction "1_37") (pintype "passive"))
      (node (ref "X4") (pin "38") (pinfunction "1_38") (pintype "passive"))
    )
    (net (code "10") (name "GPIO7") (class "Default")
      (node (ref "EXP1") (pin "8") (pinfunction "8_8") (pintype "passive"))
      (node (ref "X2") (pin "39") (pinfunction "1_39") (pintype "passive"))
      (node (ref "X2") (pin "40") (pinfunction "1_40") (pintype "passive"))
      (node (ref "X3") (pin "39") (pinfunction "1_39") (pintype "passive"))
      (node (ref "X3") (pin "40") (pinfunction "1_40") (pintype "passive"))
      (node (ref "X4") (pin "39") (pinfunction "1_39") (pintype "passive"))
      (node (ref "X4") (pin "40") (pinfunction "1_40") (pintype "passive"))
    )
    (net (code "11") (name "GPIO8") (class "Default")
      (node (ref "EXP1") (pin "9") (pinfunction "9_9") (pintype "passive"))
      (node (ref "X2") (pin "41") (pinfunction "1_41") (pintype "passive"))
      (node (ref "X2") (pin "42") (pinfunction "1_42") (pintype "passive"))
      (node (ref "X3") (pin "41") (pinfunction "1_41") (pintype "passive"))
      (node (ref "X3") (pin "42") (pinfunction "1_42") (pintype "passive"))
      (node (ref "X4") (pin "41") (pinfunction "1_41") (pintype "passive"))
      (node (ref "X4") (pin "42") (pinfunction "1_42") (pintype "passive"))
    )
    (net (code "12") (name "GPIO9") (class "Default")
      (node (ref "EXP1") (pin "10") (pinfunction "10_10") (pintype "passive"))
      (node (ref "X2") (pin "43") (pinfunction "1_43") (pintype "passive"))
      (node (ref "X2") (pin "44") (pinfunction "1_44") (pintype "passive"))
      (node (ref "X3") (pin "43") (pinfunction "1_43") (pintype "passive"))
      (node (ref "X3") (pin "44") (pinfunction "1_44") (pintype "passive"))
      (node (ref "X4") (pin "43") (pinfunction "1_43") (pintype "passive"))
      (node (ref "X4") (pin "44") (pinfunction "1_44") (pintype "passive"))
    )
    (net (code "13") (name "GPIO10") (class "Default")
      (node (ref "EXP2") (pin "1") (pinfunction "1_1") (pintype "passive"))
      (node (ref "X2") (pin "45") (pinfunction "1_45") (pintype "passive"))
      (node (ref "X2") (pin "46") (pinfunction "1_46") (pintype "passive"))
      (node (ref "X3") (pin "45") (pinfunction "1_45") (pintype "passive"))
      (node (ref "X3") (pin "46") (pinfunction "1_46") (pintype "passive"))
      (node (ref "X4") (pin "45") (pinfunction "1_45") (pintype "passive"))
      (node (ref "X4") (pin "46") (pinfunction "1_46") (pintype "passive"))
    )
    (net (code "14") (name "GPIO11") (class "Default")
      (node (ref "EXP2") (pin "2") (pinfunction "2_2") (pintype "passive"))
      (node (ref "X2") (pin "47") (pinfunction "1_47") (pintype "passive"))
      (node (ref "X2") (pin "48") (pinfunction "1_48") (pintype "passive"))
      (node (ref "X3") (pin "47") (pinfunction "1_47") (pintype "passive"))
      (node (ref "X3") (pin "48") (pinfunction "1_48") (pintype "passive"))
      (node (ref "X4") (pin "47") (pinfunction "1_47") (pintype "passive"))
      (node (ref "X4") (pin "48") (pinfunction "1_48") (pintype "passive"))
    )
    (net (code "15") (name "GPIO12") (class "Default")
      (node (ref "EXP2") (pin "3") (pinfunction "3_3") (pintype "passive"))
      (node (ref "X2") (pin "49") (pinfunction "1_49") (pintype "passive"))
      (node (ref "X2") (pin "50") (pinfunction "1_50") (pintype "passive"))
      (node (ref "X3") (pin "49") (pinfunction "1_49") (pintype "passive"))
      (node (ref "X3") (pin "50") (pinfunction "1_50") (pintype "passive"))
      (node (ref "X4") (pin "49") (pinfunction "1_49") (pintype "passive"))
      (node (ref "X4") (pin "50") (pinfunction "1_50") (pintype "passive"))
    )
    (net (code "16") (name "GPIO13") (class "Default")
      (node (ref "EXP2") (pin "4") (pinfunction "4_4") (pintype "passive"))
      (node (ref "X2") (pin "51") (pinfunction "1_51") (pintype "passive"))
      (node (ref "X2") (pin "52") (pinfunction "1_52") (pintype "passive"))
      (node (ref "X3") (pin "51") (pinfunction "1_51") (pintype "passive"))
      (node (ref "X3") (pin "52") (pinfunction "1_52") (pintype "passive"))
      (node (ref "X4") (pin "51") (pinfunction "1_51") (pintype "passive"))
      (node (ref "X4") (pin "52") (pinfunction "1_52") (pintype "passive"))
    )
    (net (code "17") (name "GPIO17") (class "Default")
      (node (ref "EXP2") (pin "7") (pinfunction "7_7") (pintype "passive"))
      (node (ref "X2") (pin "57") (pinfunction "1_57") (pintype "passive"))
      (node (ref "X2") (pin "58") (pinfunction "1_58") (pintype "passive"))
      (node (ref "X3") (pin "57") (pinfunction "1_57") (pintype "passive"))
      (node (ref "X3") (pin "58") (pinfunction "1_58") (pintype "passive"))
      (node (ref "X4") (pin "57") (pinfunction "1_57") (pintype "passive"))
      (node (ref "X4") (pin "58") (pinfunction "1_58") (pintype "passive"))
    )
    (net (code "18") (name "GPIO18") (class "Default")
      (node (ref "EXP2") (pin "8") (pinfunction "8_8") (pintype "passive"))
      (node (ref "X2") (pin "59") (pinfunction "1_59") (pintype "passive"))
      (node (ref "X2") (pin "60") (pinfunction "1_60") (pintype "passive"))
      (node (ref "X3") (pin "59") (pinfunction "1_59") (pintype "passive"))
      (node (ref "X3") (pin "60") (pinfunction "1_60") (pintype "passive"))
      (node (ref "X4") (pin "59") (pinfunction "1_59") (pintype "passive"))
      (node (ref "X4") (pin "60") (pinfunction "1_60") (pintype "passive"))
    )
    (net (code "19") (name "GPIO19") (class "Default")
      (node (ref "EXP2") (pin "9") (pinfunction "9_9") (pintype "passive"))
      (node (ref "X2") (pin "61") (pinfunction "1_61") (pintype "passive"))
      (node (ref "X2") (pin "62") (pinfunction "1_62") (pintype "passive"))
      (node (ref "X3") (pin "61") (pinfunction "1_61") (pintype "passive"))
      (node (ref "X3") (pin "62") (pinfunction "1_62") (pintype "passive"))
      (node (ref "X4") (pin "61") (pinfunction "1_61") (pintype "passive"))
      (node (ref "X4") (pin "62") (pinfunction "1_62") (pintype "passive"))
    )
    (net (code "20") (name "GPIO20") (class "Default")
      (node (ref "EXP2") (pin "10") (pinfunction "10_10") (pintype "passive"))
      (node (ref "X2") (pin "63") (pinfunction "1_63") (pintype "passive"))
      (node (ref "X2") (pin "64") (pinfunction "1_64") (pintype "passive"))
      (node (ref "X3") (pin "63") (pinfunction "1_63") (pintype "passive"))
      (node (ref "X3") (pin "64") (pinfunction "1_64") (pintype "passive"))
      (node (ref "X4") (pin "63") (pinfunction "1_63") (pintype "passive"))
      (node (ref "X4") (pin "64") (pinfunction "1_64") (pintype "passive"))
    )
    (net (code "21") (name "GPIO21") (class "Default")
      (node (ref "EXP3") (pin "1") (pinfunction "1_1") (pintype "passive"))
      (node (ref "X2") (pin "65") (pinfunction "1_65") (pintype "passive"))
      (node (ref "X2") (pin "66") (pinfunction "1_66") (pintype "passive"))
      (node (ref "X3") (pin "65") (pinfunction "1_65") (pintype "passive"))
      (node (ref "X3") (pin "66") (pinfunction "1_66") (pintype "passive"))
      (node (ref "X4") (pin "65") (pinfunction "1_65") (pintype "passive"))
      (node (ref "X4") (pin "66") (pinfunction "1_66") (pintype "passive"))
    )
    (net (code "22") (name "GPIO22") (class "Default")
      (node (ref "EXP3") (pin "2") (pinfunction "2_2") (pintype "passive"))
      (node (ref "X2") (pin "67") (pinfunction "1_67") (pintype "passive"))
      (node (ref "X2") (pin "68") (pinfunction "1_68") (pintype "passive"))
      (node (ref "X3") (pin "67") (pinfunction "1_67") (pintype "passive"))
      (node (ref "X3") (pin "68") (pinfunction "1_68") (pintype "passive"))
      (node (ref "X4") (pin "67") (pinfunction "1_67") (pintype "passive"))
      (node (ref "X4") (pin "68") (pinfunction "1_68") (pintype "passive"))
    )
    (net (code "23") (name "GPIO23") (class "Default")
      (node (ref "EXP3") (pin "3") (pinfunction "3_3") (pintype "passive"))
      (node (ref "X2") (pin "69") (pinfunction "1_69") (pintype "passive"))
      (node (ref "X2") (pin "70") (pinfunction "1_70") (pintype "passive"))
      (node (ref "X3") (pin "69") (pinfunction "1_69") (pintype "passive"))
      (node (ref "X3") (pin "70") (pinfunction "1_70") (pintype "passive"))
      (node (ref "X4") (pin "69") (pinfunction "1_69") (pintype "passive"))
      (node (ref "X4") (pin "70") (pinfunction "1_70") (pintype "passive"))
    )
    (net (code "24") (name "GPIO24") (class "Default")
      (node (ref "EXP3") (pin "4") (pinfunction "4_4") (pintype "passive"))
      (node (ref "X2") (pin "71") (pinfunction "1_71") (pintype "passive"))
      (node (ref "X2") (pin "72") (pinfunction "1_72") (pintype "passive"))
      (node (ref "X3") (pin "71") (pinfunction "1_71") (pintype "passive"))
      (node (ref "X3") (pin "72") (pinfunction "1_72") (pintype "passive"))
      (node (ref "X4") (pin "71") (pinfunction "1_71") (pintype "passive"))
      (node (ref "X4") (pin "72") (pinfunction "1_72") (pintype "passive"))
    )
    (net (code "25") (name "GPIO25") (class "Default")
      (node (ref "EXP3") (pin "5") (pinfunction "5_5") (pintype "passive"))
      (node (ref "X2") (pin "73") (pinfunction "1_73") (pintype "passive"))
      (node (ref "X2") (pin "74") (pinfunction "1_74") (pintype "passive"))
      (node (ref "X3") (pin "73") (pinfunction "1_73") (pintype "passive"))
      (node (ref "X3") (pin "74") (pinfunction "1_74") (pintype "passive"))
      (node (ref "X4") (pin "73") (pinfunction "1_73") (pintype "passive"))
      (node (ref "X4") (pin "74") (pinfunction "1_74") (pintype "passive"))
    )
    (net (code "26") (name "GPIO26") (class "Default")
      (node (ref "EXP3") (pin "6") (pinfunction "6_6") (pintype "passive"))
      (node (ref "X2") (pin "75") (pinfunction "1_75") (pintype "passive"))
      (node (ref "X2") (pin "76") (pinfunction "1_76") (pintype "passive"))
      (node (ref "X3") (pin "75") (pinfunction "1_75") (pintype "passive"))
      (node (ref "X3") (pin "76") (pinfunction "1_76") (pintype "passive"))
      (node (ref "X4") (pin "75") (pinfunction "1_75") (pintype "passive"))
      (node (ref "X4") (pin "76") (pinfunction "1_76") (pintype "passive"))
    )
    (net (code "27") (name "GPIO27") (class "Default")
      (node (ref "EXP3") (pin "7") (pinfunction "7_7") (pintype "passive"))
      (node (ref "X2") (pin "77") (pinfunction "1_77") (pintype "passive"))
      (node (ref "X2") (pin "78") (pinfunction "1_78") (pintype "passive"))
      (node (ref "X3") (pin "77") (pinfunction "1_77") (pintype "passive"))
      (node (ref "X3") (pin "78") (pinfunction "1_78") (pintype "passive"))
      (node (ref "X4") (pin "77") (pinfunction "1_77") (pintype "passive"))
      (node (ref "X4") (pin "78") (pinfunction "1_78") (pintype "passive"))
    )
    (net (code "28") (name "GPIO28") (class "Default")
      (node (ref "EXP3") (pin "8") (pinfunction "8_8") (pintype "passive"))
      (node (ref "X2") (pin "79") (pinfunction "1_79") (pintype "passive"))
      (node (ref "X2") (pin "80") (pinfunction "1_80") (pintype "passive"))
      (node (ref "X3") (pin "79") (pinfunction "1_79") (pintype "passive"))
      (node (ref "X3") (pin "80") (pinfunction "1_80") (pintype "passive"))
      (node (ref "X4") (pin "79") (pinfunction "1_79") (pintype "passive"))
      (node (ref "X4") (pin "80") (pinfunction "1_80") (pintype "passive"))
    )
    (net (code "29") (name "GPIO29") (class "Default")
      (node (ref "EXP3") (pin "9") (pinfunction "9_9") (pintype "passive"))
      (node (ref "X2") (pin "81") (pinfunction "1_81") (pintype "passive"))
      (node (ref "X2") (pin "82") (pinfunction "1_82") (pintype "passive"))
      (node (ref "X3") (pin "81") (pinfunction "1_81") (pintype "passive"))
      (node (ref "X3") (pin "82") (pinfunction "1_82") (pintype "passive"))
      (node (ref "X4") (pin "81") (pinfunction "1_81") (pintype "passive"))
      (node (ref "X4") (pin "82") (pinfunction "1_82") (pintype "passive"))
    )
    (net (code "30") (name "GPIO30") (class "Default")
      (node (ref "EXP3") (pin "10") (pinfunction "10_10") (pintype "passive"))
      (node (ref "X2") (pin "83") (pinfunction "1_83") (pintype "passive"))
      (node (ref "X2") (pin "84") (pinfunction "1_84") (pintype "passive"))
      (node (ref "X3") (pin "83") (pinfunction "1_83") (pintype "passive"))
      (node (ref "X3") (pin "84") (pinfunction "1_84") (pintype "passive"))
      (node (ref "X4") (pin "83") (pinfunction "1_83") (pintype "passive"))
      (node (ref "X4") (pin "84") (pinfunction "1_84") (pintype "passive"))
    )
    (net (code "31") (name "GPIO31") (class "Default")
      (node (ref "EXP4") (pin "1") (pinfunction "1_1") (pintype "passive"))
      (node (ref "X2") (pin "85") (pinfunction "1_85") (pintype "passive"))
      (node (ref "X2") (pin "86") (pinfunction "1_86") (pintype "passive"))
      (node (ref "X3") (pin "85") (pinfunction "1_85") (pintype "passive"))
      (node (ref "X3") (pin "86") (pinfunction "1_86") (pintype "passive"))
      (node (ref "X4") (pin "85") (pinfunction "1_85") (pintype "passive"))
      (node (ref "X4") (pin "86") (pinfunction "1_86") (pintype "passive"))
    )
    (net (code "32") (name "GPIO32") (class "Default")
      (node (ref "EXP4") (pin "2") (pinfunction "2_2") (pintype "passive"))
      (node (ref "X2") (pin "87") (pinfunction "1_87") (pintype "passive"))
      (node (ref "X2") (pin "88") (pinfunction "1_88") (pintype "passive"))
      (node (ref "X3") (pin "87") (pinfunction "1_87") (pintype "passive"))
      (node (ref "X3") (pin "88") (pinfunction "1_88") (pintype "passive"))
      (node (ref "X4") (pin "87") (pinfunction "1_87") (pintype "passive"))
      (node (ref "X4") (pin "88") (pinfunction "1_88") (pintype "passive"))
    )
    (net (code "33") (name "GPIO33") (class "Default")
      (node (ref "EXP4") (pin "3") (pinfunction "3_3") (pintype "passive"))
      (node (ref "X2") (pin "89") (pinfunction "1_89") (pintype "passive"))
      (node (ref "X2") (pin "90") (pinfunction "1_90") (pintype "passive"))
      (node (ref "X3") (pin "89") (pinfunction "1_89") (pintype "passive"))
      (node (ref "X3") (pin "90") (pinfunction "1_90") (pintype "passive"))
      (node (ref "X4") (pin "89") (pinfunction "1_89") (pintype "passive"))
      (node (ref "X4") (pin "90") (pinfunction "1_90") (pintype "passive"))
    )
    (net (code "34") (name "GPIO34") (class "Default")
      (node (ref "EXP4") (pin "4") (pinfunction "4_4") (pintype "passive"))
      (node (ref "X2") (pin "91") (pinfunction "1_91") (pintype "passive"))
      (node (ref "X2") (pin "92") (pinfunction "1_92") (pintype "passive"))
      (node (ref "X3") (pin "91") (pinfunction "1_91") (pintype "passive"))
      (node (ref "X3") (pin "92") (pinfunction "1_92") (pintype "passive"))
      (node (ref "X4") (pin "91") (pinfunction "1_91") (pintype "passive"))
      (node (ref "X4") (pin "92") (pinfunction "1_92") (pintype "passive"))
    )
    (net (code "35") (name "GPIO35") (class "Default")
      (node (ref "EXP4") (pin "5") (pinfunction "5_5") (pintype "passive"))
      (node (ref "X2") (pin "93") (pinfunction "1_93") (pintype "passive"))
      (node (ref "X2") (pin "94") (pinfunction "1_94") (pintype "passive"))
      (node (ref "X3") (pin "93") (pinfunction "1_93") (pintype "passive"))
      (node (ref "X3") (pin "94") (pinfunction "1_94") (pintype "passive"))
      (node (ref "X4") (pin "93") (pinfunction "1_93") (pintype "passive"))
      (node (ref "X4") (pin "94") (pinfunction "1_94") (pintype "passive"))
    )
    (net (code "36") (name "GPIO36") (class "Default")
      (node (ref "EXP4") (pin "6") (pinfunction "6_6") (pintype "passive"))
      (node (ref "X2") (pin "95") (pinfunction "1_95") (pintype "passive"))
      (node (ref "X2") (pin "96") (pinfunction "1_96") (pintype "passive"))
      (node (ref "X3") (pin "95") (pinfunction "1_95") (pintype "passive"))
      (node (ref "X3") (pin "96") (pinfunction "1_96") (pintype "passive"))
      (node (ref "X4") (pin "95") (pinfunction "1_95") (pintype "passive"))
      (node (ref "X4") (pin "96") (pinfunction "1_96") (pintype "passive"))
    )
    (net (code "37") (name "GPIO37") (class "Default")
      (node (ref "EXP4") (pin "7") (pinfunction "7_7") (pintype "passive"))
      (node (ref "X2") (pin "97") (pinfunction "1_97") (pintype "passive"))
      (node (ref "X2") (pin "98") (pinfunction "1_98") (pintype "passive"))
      (node (ref "X3") (pin "97") (pinfunction "1_97") (pintype "passive"))
      (node (ref "X3") (pin "98") (pinfunction "1_98") (pintype "passive"))
      (node (ref "X4") (pin "97") (pinfunction "1_97") (pintype "passive"))
      (node (ref "X4") (pin "98") (pinfunction "1_98") (pintype "passive"))
    )
    (net (code "38") (name "GPIO38") (class "Default")
      (node (ref "EXP4") (pin "8") (pinfunction "8_8") (pintype "passive"))
      (node (ref "X2") (pin "100") (pinfunction "1_100") (pintype "passive"))
      (node (ref "X2") (pin "99") (pinfunction "1_99") (pintype "passive"))
      (node (ref "X3") (pin "100") (pinfunction "1_100") (pintype "passive"))
      (node (ref "X3") (pin "99") (pinfunction "1_99") (pintype "passive"))
      (node (ref "X4") (pin "100") (pinfunction "1_100") (pintype "passive"))
      (node (ref "X4") (pin "99") (pinfunction "1_99") (pintype "passive"))
    )
    (net (code "39") (name "GPIO39") (class "Default")
      (node (ref "EXP4") (pin "9") (pinfunction "9_9") (pintype "passive"))
      (node (ref "X2") (pin "101") (pinfunction "1_101") (pintype "passive"))
      (node (ref "X2") (pin "102") (pinfunction "1_102") (pintype "passive"))
      (node (ref "X3") (pin "101") (pinfunction "1_101") (pintype "passive"))
      (node (ref "X3") (pin "102") (pinfunction "1_102") (pintype "passive"))
      (node (ref "X4") (pin "101") (pinfunction "1_101") (pintype "passive"))
      (node (ref "X4") (pin "102") (pinfunction "1_102") (pintype "passive"))
    )
    (net (code "40") (name "GPIO40") (class "Default")
      (node (ref "EXP4") (pin "10") (pinfunction "10_10") (pintype "passive"))
      (node (ref "X2") (pin "103") (pinfunction "1_103") (pintype "passive"))
      (node (ref "X2") (pin "104") (pinfunction "1_104") (pintype "passive"))
      (node (ref "X3") (pin "103") (pinfunction "1_103") (pintype "passive"))
      (node (ref "X3") (pin "104") (pinfunction "1_104") (pintype "passive"))
      (node (ref "X4") (pin "103") (pinfunction "1_103") (pintype "passive"))
      (node (ref "X4") (pin "104") (pinfunction "1_104") (pintype "passive"))
    )
    (net (code "41") (name "GPIO41") (class "Default")
      (node (ref "EXP5") (pin "1") (pinfunction "1_1") (pintype "passive"))
      (node (ref "X2") (pin "105") (pinfunction "1_105") (pintype "passive"))
      (node (ref "X2") (pin "106") (pinfunction "1_106") (pintype "passive"))
      (node (ref "X3") (pin "105") (pinfunction "1_105") (pintype "passive"))
      (node (ref "X3") (pin "106") (pinfunction "1_106") (pintype "passive"))
      (node (ref "X4") (pin "105") (pinfunction "1_105") (pintype "passive"))
      (node (ref "X4") (pin "106") (pinfunction "1_106") (pintype "passive"))
    )
    (net (code "42") (name "GPIO42") (class "Default")
      (node (ref "EXP5") (pin "2") (pinfunction "2_2") (pintype "passive"))
      (node (ref "X2") (pin "107") (pinfunction "1_107") (pintype "passive"))
      (node (ref "X2") (pin "108") (pinfunction "1_108") (pintype "passive"))
      (node (ref "X3") (pin "107") (pinfunction "1_107") (pintype "passive"))
      (node (ref "X3") (pin "108") (pinfunction "1_108") (pintype "passive"))
      (node (ref "X4") (pin "107") (pinfunction "1_107") (pintype "passive"))
      (node (ref "X4") (pin "108") (pinfunction "1_108") (pintype "passive"))
    )
    (net (code "43") (name "GPIO43") (class "Default")
      (node (ref "EXP5") (pin "3") (pinfunction "3_3") (pintype "passive"))
      (node (ref "X2") (pin "109") (pinfunction "1_109") (pintype "passive"))
      (node (ref "X2") (pin "110") (pinfunction "1_110") (pintype "passive"))
      (node (ref "X3") (pin "109") (pinfunction "1_109") (pintype "passive"))
      (node (ref "X3") (pin "110") (pinfunction "1_110") (pintype "passive"))
      (node (ref "X4") (pin "109") (pinfunction "1_109") (pintype "passive"))
      (node (ref "X4") (pin "110") (pinfunction "1_110") (pintype "passive"))
    )
    (net (code "44") (name "GPIO44") (class "Default")
      (node (ref "EXP5") (pin "4") (pinfunction "4_4") (pintype "passive"))
      (node (ref "X2") (pin "111") (pinfunction "1_111") (pintype "passive"))
      (node (ref "X2") (pin "112") (pinfunction "1_112") (pintype "passive"))
      (node (ref "X3") (pin "111") (pinfunction "1_111") (pintype "passive"))
      (node (ref "X3") (pin "112") (pinfunction "1_112") (pintype "passive"))
      (node (ref "X4") (pin "111") (pinfunction "1_111") (pintype "passive"))
      (node (ref "X4") (pin "112") (pinfunction "1_112") (pintype "passive"))
    )
    (net (code "45") (name "GPIO45") (class "Default")
      (node (ref "EXP5") (pin "5") (pinfunction "5_5") (pintype "passive"))
      (node (ref "X2") (pin "113") (pinfunction "1_113") (pintype "passive"))
      (node (ref "X2") (pin "114") (pinfunction "1_114") (pintype "passive"))
      (node (ref "X3") (pin "113") (pinfunction "1_113") (pintype "passive"))
      (node (ref "X3") (pin "114") (pinfunction "1_114") (pintype "passive"))
      (node (ref "X4") (pin "113") (pinfunction "1_113") (pintype "passive"))
      (node (ref "X4") (pin "114") (pinfunction "1_114") (pintype "passive"))
    )
    (net (code "46") (name "N$27") (class "Default")
      (node (ref "U1") (pin "45") (pinfunction "CLK24_OUT_45") (pintype "bidirectional"))
    )
    (net (code "47") (name "NC") (class "Default")
      (node (ref "EXP5") (pin "6") (pinfunction "6_6") (pintype "passive"))
    )
    (net (code "48") (name "Net-(IC1-OUT)") (class "Default")
      (node (ref "D1") (pin "C") (pinfunction "C_C") (pintype "passive"))
      (node (ref "IC1") (pin "2") (pinfunction "OUT_2") (pintype "output"))
      (node (ref "L1") (pin "1") (pinfunction "1_1") (pintype "passive"))
    )
    (net (code "49") (name "Net-(R1-1)") (class "Default")
      (node (ref "C6") (pin "1") (pinfunction "1_1") (pintype "passive"))
      (node (ref "R1") (pin "P$1") (pinfunction "1_P$1") (pintype "passive"))
      (node (ref "U1") (pin "52") (pinfunction "RX_P_52") (pintype "bidirectional"))
      (node (ref "X1") (pin "4") (pinfunction "RD+_4") (pintype "input"))
    )
    (net (code "50") (name "Net-(R2-1)") (class "Default")
      (node (ref "C7") (pin "1") (pinfunction "1_1") (pintype "passive"))
      (node (ref "R2") (pin "P$1") (pinfunction "1_P$1") (pintype "passive"))
      (node (ref "U1") (pin "53") (pinfunction "RX_N_53") (pintype "bidirectional"))
      (node (ref "X1") (pin "6") (pinfunction "RD-_6") (pintype "input"))
    )
    (net (code "51") (name "Net-(R3-1)") (class "Default")
      (node (ref "C8") (pin "1") (pinfunction "1_1") (pintype "passive"))
      (node (ref "R3") (pin "P$1") (pinfunction "1_P$1") (pintype "passive"))
      (node (ref "U1") (pin "55") (pinfunction "TX_P_55") (pintype "bidirectional"))
      (node (ref "X1") (pin "1") (pinfunction "TD+_1") (pintype "input"))
    )
    (net (code "52") (name "Net-(R4-1)") (class "Default")
      (node (ref "C9") (pin "1") (pinfunction "1_1") (pintype "passive"))
      (node (ref "R4") (pin "P$1") (pinfunction "1_P$1") (pintype "passive"))
      (node (ref "U1") (pin "56") (pinfunction "TX_N_56") (pintype "bidirectional"))
      (node (ref "X1") (pin "3") (pinfunction "TD-_3") (pintype "input"))
    )
    (net (code "53") (name "Net-(R5-1)") (class "Default")
      (node (ref "R5") (pin "P$1") (pinfunction "1_P$1") (pintype "passive"))
      (node (ref "U1") (pin "41") (pinfunction "AUTOMDIX_EN_41") (pintype "bidirectional"))
    )
    (net (code "54") (name "Net-(R6-2)") (class "Default")
      (node (ref "R6") (pin "P$2") (pinfunction "2_P$2") (pintype "passive"))
      (node (ref "U1") (pin "50") (pinfunction "EXTRES_50") (pintype "bidirectional"))
    )
    (net (code "55") (name "Net-(R7-1)") (class "Default")
      (node (ref "C11") (pin "2") (pinfunction "2_2") (pintype "passive"))
      (node (ref "R7") (pin "P$1") (pinfunction "1_P$1") (pintype "passive"))
      (node (ref "Y1") (pin "1") (pinfunction "1_1") (pintype "passive"))
    )
    (net (code "56") (name "Net-(R7-2)") (class "Default")
      (node (ref "R7") (pin "P$2") (pinfunction "2_P$2") (pintype "passive"))
      (node (ref "U1") (pin "60") (pinfunction "XO_60") (pintype "bidirectional"))
    )
    (net (code "57") (name "Net-(U1B-XI)") (class "Default")
      (node (ref "C10") (pin "2") (pinfunction "2_2") (pintype "passive"))
      (node (ref "U1") (pin "61") (pinfunction "XI_61") (pintype "bidirectional"))
      (node (ref "Y1") (pin "2") (pinfunction "2_2") (pintype "passive"))
    )
    (net (code "58") (name "Net-(U1B-~{LNKA_LED})") (class "Default")
      (node (ref "U1") (pin "21") (pinfunction "~{LNKA_LED}_21") (pintype "bidirectional"))
      (node (ref "X1") (pin "9") (pinfunction "C-R_9") (pintype "passive"))
    )
    (net (code "59") (name "Net-(U1B-~{SPD_LED})") (class "Default")
      (node (ref "U1") (pin "22") (pinfunction "~{SPD_LED}_22") (pintype "bidirectional"))
      (node (ref "X1") (pin "11") (pinfunction "C-L_11") (pintype "passive"))
    )
    (net (code "60") (name "RXD0") (class "Default")
      (node (ref "EXP2") (pin "6") (pinfunction "6_6") (pintype "passive"))
      (node (ref "X2") (pin "55") (pinfunction "1_55") (pintype "passive"))
      (node (ref "X2") (pin "56") (pinfunction "1_56") (pintype "passive"))
      (node (ref "X3") (pin "55") (pinfunction "1_55") (pintype "passive"))
      (node (ref "X3") (pin "56") (pinfunction "1_56") (pintype "passive"))
      (node (ref "X4") (pin "55") (pinfunction "1_55") (pintype "passive"))
      (node (ref "X4") (pin "56") (pinfunction "1_56") (pintype "passive"))
    )
    (net (code "61") (name "SCL") (class "Default")
      (node (ref "EXP1") (pin "2") (pinfunction "2_2") (pintype "passive"))
      (node (ref "X2") (pin "27") (pinfunction "1_27") (pintype "passive"))
      (node (ref "X2") (pin "28") (pinfunction "1_28") (pintype "passive"))
      (node (ref "X3") (pin "27") (pinfunction "1_27") (pintype "passive"))
      (node (ref "X3") (pin "28") (pinfunction "1_28") (pintype "passive"))
      (node (ref "X4") (pin "27") (pinfunction "1_27") (pintype "passive"))
      (node (ref "X4") (pin "28") (pinfunction "1_28") (pintype "passive"))
    )
    (net (code "62") (name "SCL1") (class "Default")
      (node (ref "EXP1") (pin "4") (pinfunction "4_4") (pintype "passive"))
      (node (ref "X2") (pin "31") (pinfunction "1_31") (pintype "passive"))
      (node (ref "X2") (pin "32") (pinfunction "1_32") (pintype "passive"))
      (node (ref "X3") (pin "31") (pinfunction "1_31") (pintype "passive"))
      (node (ref "X3") (pin "32") (pinfunction "1_32") (pintype "passive"))
      (node (ref "X4") (pin "31") (pinfunction "1_31") (pintype "passive"))
      (node (ref "X4") (pin "32") (pinfunction "1_32") (pintype "passive"))
    )
    (net (code "63") (name "SDA") (class "Default")
      (node (ref "EXP1") (pin "1") (pinfunction "1_1") (pintype "passive"))
      (node (ref "X2") (pin "25") (pinfunction "1_25") (pintype "passive"))
      (node (ref "X2") (pin "26") (pinfunction "1_26") (pintype "passive"))
      (node (ref "X3") (pin "25") (pinfunction "1_25") (pintype "passive"))
      (node (ref "X3") (pin "26") (pinfunction "1_26") (pintype "passive"))
      (node (ref "X4") (pin "25") (pinfunction "1_25") (pintype "passive"))
      (node (ref "X4") (pin "26") (pinfunction "1_26") (pintype "passive"))
    )
    (net (code "64") (name "SDA1") (class "Default")
      (node (ref "EXP1") (pin "3") (pinfunction "3_3") (pintype "passive"))
      (node (ref "X2") (pin "29") (pinfunction "1_29") (pintype "passive"))
      (node (ref "X2") (pin "30") (pinfunction "1_30") (pintype "passive"))
      (node (ref "X3") (pin "29") (pinfunction "1_29") (pintype "passive"))
      (node (ref "X3") (pin "30") (pinfunction "1_30") (pintype "passive"))
      (node (ref "X4") (pin "29") (pinfunction "1_29") (pintype "passive"))
      (node (ref "X4") (pin "30") (pinfunction "1_30") (pintype "passive"))
    )
    (net (code "65") (name "TXD0") (class "Default")
      (node (ref "EXP2") (pin "5") (pinfunction "5_5") (pintype "passive"))
      (node (ref "X2") (pin "53") (pinfunction "1_53") (pintype "passive"))
      (node (ref "X2") (pin "54") (pinfunction "1_54") (pintype "passive"))
      (node (ref "X3") (pin "53") (pinfunction "1_53") (pintype "passive"))
      (node (ref "X3") (pin "54") (pinfunction "1_54") (pintype "passive"))
      (node (ref "X4") (pin "53") (pinfunction "1_53") (pintype "passive"))
      (node (ref "X4") (pin "54") (pinfunction "1_54") (pintype "passive"))
    )
    (net (code "66") (name "USB+") (class "Default")
      (node (ref "EXP5") (pin "10") (pinfunction "10_10") (pintype "passive"))
      (node (ref "U1") (pin "59") (pinfunction "USB_DP0_P_59") (pintype "bidirectional"))
    )
    (net (code "67") (name "USB-") (class "Default")
      (node (ref "EXP5") (pin "9") (pinfunction "9_9") (pintype "passive"))
      (node (ref "U1") (pin "58") (pinfunction "USB_DM0_N_58") (pintype "bidirectional"))
    )
    (net (code "68") (name "USB2+") (class "Default")
      (node (ref "U1") (pin "2") (pinfunction "USB_DP2_P_2") (pintype "bidirectional"))
      (node (ref "X2") (pin "1") (pinfunction "1_1") (pintype "passive"))
      (node (ref "X2") (pin "2") (pinfunction "1_2") (pintype "passive"))
    )
    (net (code "69") (name "USB2-") (class "Default")
      (node (ref "U1") (pin "1") (pinfunction "USB_DM2_N_1") (pintype "bidirectional"))
      (node (ref "X2") (pin "3") (pinfunction "1_3") (pintype "passive"))
      (node (ref "X2") (pin "4") (pinfunction "1_4") (pintype "passive"))
    )
    (net (code "70") (name "USB2_PWR") (class "Default")
      (node (ref "U1") (pin "14") (pinfunction "PRTCTRL2_14") (pintype "bidirectional"))
      (node (ref "X2") (pin "5") (pinfunction "1_5") (pintype "passive"))
      (node (ref "X2") (pin "6") (pinfunction "1_6") (pintype "passive"))
    )
    (net (code "71") (name "USB3+") (class "Default")
      (node (ref "U1") (pin "4") (pinfunction "USB_DP3_P_4") (pintype "bidirectional"))
      (node (ref "X3") (pin "1") (pinfunction "1_1") (pintype "passive"))
      (node (ref "X3") (pin "2") (pinfunction "1_2") (pintype "passive"))
    )
    (net (code "72") (name "USB3-") (class "Default")
      (node (ref "U1") (pin "3") (pinfunction "USB_DM3_N_3") (pintype "bidirectional"))
      (node (ref "X3") (pin "3") (pinfunction "1_3") (pintype "passive"))
      (node (ref "X3") (pin "4") (pinfunction "1_4") (pintype "passive"))
    )
    (net (code "73") (name "USB3_PWR") (class "Default")
      (node (ref "U1") (pin "16") (pinfunction "PRTCTRL3_16") (pintype "bidirectional"))
      (node (ref "X3") (pin "5") (pinfunction "1_5") (pintype "passive"))
      (node (ref "X3") (pin "6") (pinfunction "1_6") (pintype "passive"))
    )
    (net (code "74") (name "USB4+") (class "Default")
      (node (ref "U1") (pin "7") (pinfunction "USB_DP4_P_7") (pintype "bidirectional"))
      (node (ref "X4") (pin "1") (pinfunction "1_1") (pintype "passive"))
      (node (ref "X4") (pin "2") (pinfunction "1_2") (pintype "passive"))
    )
    (net (code "75") (name "USB4-") (class "Default")
      (node (ref "U1") (pin "6") (pinfunction "USB_DM4_N_6") (pintype "bidirectional"))
      (node (ref "X4") (pin "3") (pinfunction "1_3") (pintype "passive"))
      (node (ref "X4") (pin "4") (pinfunction "1_4") (pintype "passive"))
    )
    (net (code "76") (name "USB4_PWR") (class "Default")
      (node (ref "U1") (pin "17") (pinfunction "PRTCTRL4_17") (pintype "bidirectional"))
      (node (ref "X4") (pin "5") (pinfunction "1_5") (pintype "passive"))
      (node (ref "X4") (pin "6") (pinfunction "1_6") (pintype "passive"))
    )
    (net (code "77") (name "USB5+") (class "Default")
      (node (ref "JP1") (pin "D+") (pinfunction "D+_D+") (pintype "bidirectional"))
      (node (ref "U1") (pin "9") (pinfunction "USB_DP5_P_9") (pintype "bidirectional"))
    )
    (net (code "78") (name "USB5-") (class "Default")
      (node (ref "JP1") (pin "D-") (pinfunction "D-_D-") (pintype "bidirectional"))
      (node (ref "U1") (pin "8") (pinfunction "USB_DM5_N_8") (pintype "bidirectional"))
    )
    (net (code "79") (name "USB5_PWR") (class "Default")
      (node (ref "JP1") (pin "VBUS") (pinfunction "VBUS_VBUS") (pintype "bidirectional"))
      (node (ref "U1") (pin "18") (pinfunction "PRTCTRL5_18") (pintype "bidirectional"))
    )
    (net (code "80") (name "V+") (class "Default")
      (node (ref "EXP6") (pin "10") (pinfunction "10_10") (pintype "passive"))
      (node (ref "EXP6") (pin "9") (pinfunction "9_9") (pintype "passive"))
      (node (ref "IC1") (pin "1") (pinfunction "IN_1") (pintype "input"))
      (node (ref "X2") (pin "19") (pinfunction "1_19") (pintype "passive"))
      (node (ref "X2") (pin "20") (pinfunction "1_20") (pintype "passive"))
      (node (ref "X2") (pin "21") (pinfunction "1_21") (pintype "passive"))
      (node (ref "X2") (pin "22") (pinfunction "1_22") (pintype "passive"))
      (node (ref "X2") (pin "23") (pinfunction "1_23") (pintype "passive"))
      (node (ref "X2") (pin "24") (pinfunction "1_24") (pintype "passive"))
      (node (ref "X3") (pin "19") (pinfunction "1_19") (pintype "passive"))
      (node (ref "X3") (pin "20") (pinfunction "1_20") (pintype "passive"))
      (node (ref "X3") (pin "21") (pinfunction "1_21") (pintype "passive"))
      (node (ref "X3") (pin "22") (pinfunction "1_22") (pintype "passive"))
      (node (ref "X3") (pin "23") (pinfunction "1_23") (pintype "passive"))
      (node (ref "X3") (pin "24") (pinfunction "1_24") (pintype "passive"))
      (node (ref "X4") (pin "19") (pinfunction "1_19") (pintype "passive"))
      (node (ref "X4") (pin "20") (pinfunction "1_20") (pintype "passive"))
      (node (ref "X4") (pin "21") (pinfunction "1_21") (pintype "passive"))
      (node (ref "X4") (pin "22") (pinfunction "1_22") (pintype "passive"))
      (node (ref "X4") (pin "23") (pinfunction "1_23") (pintype "passive"))
      (node (ref "X4") (pin "24") (pinfunction "1_24") (pintype "passive"))
    )
    (net (code "81") (name "VBUS_DET") (class "Default")
      (node (ref "R8") (pin "1") (pinfunction "1_1") (pintype "passive"))
      (node (ref "U1") (pin "11") (pinfunction "VBUS_DET_11") (pintype "bidirectional"))
    )
    (net (code "82") (name "VDD18CORE") (class "Default")
      (node (ref "C18") (pin "1") (pinfunction "1_1") (pintype "passive"))
      (node (ref "C19") (pin "1") (pinfunction "1_1") (pintype "passive"))
      (node (ref "C20") (pin "1") (pinfunction "1_1") (pintype "passive"))
      (node (ref "U1") (pin "15") (pinfunction "VDD_1V8_CORE1_15") (pintype "bidirectional"))
      (node (ref "U1") (pin "38") (pinfunction "VDD_1V8_CORE2_38") (pintype "bidirectional"))
    )
    (net (code "83") (name "VDDA33") (class "Default")
      (node (ref "C14") (pin "1") (pinfunction "1_1") (pintype "passive"))
      (node (ref "C15") (pin "1") (pinfunction "1_1") (pintype "passive"))
      (node (ref "R1") (pin "P$2") (pinfunction "2_P$2") (pintype "passive"))
      (node (ref "R2") (pin "P$2") (pinfunction "2_P$2") (pintype "passive"))
      (node (ref "R3") (pin "P$2") (pinfunction "2_P$2") (pintype "passive"))
      (node (ref "R4") (pin "P$2") (pinfunction "2_P$2") (pintype "passive"))
      (node (ref "R9") (pin "2") (pinfunction "2_2") (pintype "passive"))
    )
    (net (code "84") (name "unconnected-(U1A-EECLK-Pad23)") (class "Default")
      (node (ref "U1") (pin "23") (pinfunction "EECLK_23") (pintype "bidirectional"))
    )
    (net (code "85") (name "unconnected-(U1A-EECS-Pad24)") (class "Default")
      (node (ref "U1") (pin "24") (pinfunction "EECS_24") (pintype "bidirectional"))
    )
    (net (code "86") (name "unconnected-(U1A-EEDI-Pad26)") (class "Default")
      (node (ref "U1") (pin "26") (pinfunction "EEDI_26") (pintype "bidirectional"))
    )
    (net (code "87") (name "unconnected-(U1A-EEDO-Pad25)") (class "Default")
      (node (ref "U1") (pin "25") (pinfunction "EEDO_25") (pintype "bidirectional"))
    )
    (net (code "88") (name "unconnected-(U1B-~{FDX_LED}-Pad20)") (class "Default")
      (node (ref "U1") (pin "20") (pinfunction "~{FDX_LED}_20") (pintype "bidirectional"))
    )
    (net (code "89") (name "unconnected-(U1C-GPIO3-Pad35)") (class "Default")
      (node (ref "U1") (pin "35") (pinfunction "GPIO3_35") (pintype "bidirectional"))
    )
    (net (code "90") (name "unconnected-(U1C-GPIO4-Pad36)") (class "Default")
      (node (ref "U1") (pin "36") (pinfunction "GPIO4_36") (pintype "bidirectional"))
    )
    (net (code "91") (name "unconnected-(U1C-GPIO5-Pad37)") (class "Default")
      (node (ref "U1") (pin "37") (pinfunction "GPIO5_37") (pintype "bidirectional"))
    )
    (net (code "92") (name "unconnected-(U1C-GPIO6-Pad42)") (class "Default")
      (node (ref "U1") (pin "42") (pinfunction "GPIO6_42") (pintype "bidirectional"))
    )
    (net (code "93") (name "unconnected-(U1C-GPIO7-Pad43)") (class "Default")
      (node (ref "U1") (pin "43") (pinfunction "GPIO7_43") (pintype "bidirectional"))
    )
    (net (code "94") (name "unconnected-(U1D-TCK-Pad32)") (class "Default")
      (node (ref "U1") (pin "32") (pinfunction "TCK_32") (pintype "bidirectional"))
    )
    (net (code "95") (name "unconnected-(U1D-TDI-Pad30)") (class "Default")
      (node (ref "U1") (pin "30") (pinfunction "TDI_30") (pintype "bidirectional"))
    )
    (net (code "96") (name "unconnected-(U1D-TDO-Pad31)") (class "Default")
      (node (ref "U1") (pin "31") (pinfunction "TDO_31") (pintype "bidirectional"))
    )
    (net (code "97") (name "unconnected-(U1D-TMS-Pad29)") (class "Default")
      (node (ref "U1") (pin "29") (pinfunction "TMS_29") (pintype "bidirectional"))
    )
    (net (code "98") (name "unconnected-(U1D-~{TRST}-Pad28)") (class "Default")
      (node (ref "U1") (pin "28") (pinfunction "~{TRST}_28") (pintype "bidirectional"))
    )
    (net (code "99") (name "unconnected-(U1E-TEST1-Pad13)") (class "Default")
      (node (ref "U1") (pin "13") (pinfunction "TEST1_13") (pintype "bidirectional"))
    )
    (net (code "100") (name "unconnected-(U1E-TEST2-Pad34)") (class "Default")
      (node (ref "U1") (pin "34") (pinfunction "TEST2_34") (pintype "bidirectional"))
    )
    (net (code "101") (name "unconnected-(U1E-TEST3-Pad40)") (class "Default")
      (node (ref "U1") (pin "40") (pinfunction "TEST3_40") (pintype "bidirectional"))
    )
    (net (code "102") (name "unconnected-(U1E-TEST4-Pad47)") (class "Default")
      (node (ref "U1") (pin "47") (pinfunction "TEST4_47") (pintype "bidirectional"))
    )
    (net (code "103") (name "unconnected-(U1E-VDD_1V8_ETH_PLL-Pad48)") (class "Default")
      (node (ref "U1") (pin "48") (pinfunction "VDD_1V8_ETH_PLL_48") (pintype "bidirectional"))
    )
    (net (code "104") (name "unconnected-(U1E-VDD_1V8_USB_PLL-Pad62)") (class "Default")
      (node (ref "U1") (pin "62") (pinfunction "VDD_1V8_USB_PLL_62") (pintype "bidirectional"))
    )
    (net (code "105") (name "unconnected-(U1E-VDD_GND_TAB-PadPAD)") (class "Default")
      (node (ref "U1") (pin "PAD") (pinfunction "VDD_GND_TAB_PAD") (pintype "bidirectional"))
    )
    (net (code "106") (name "unconnected-(U1E-~{RESET}-Pad12)") (class "Default")
      (node (ref "U1") (pin "12") (pinfunction "~{RESET}_12") (pintype "bidirectional"))
    )
    (net (code "107") (name "unconnected-(U1F-CLK24_EN-Pad44)") (class "Default")
      (node (ref "U1") (pin "44") (pinfunction "CLK24_EN_44") (pintype "bidirectional"))
    )
    (net (code "108") (name "unconnected-(U1F-USB_RBIAS-Pad63)") (class "Default")
      (node (ref "U1") (pin "63") (pinfunction "USB_RBIAS_63") (pintype "bidirectional"))
    )
    (net (code "109") (name "unconnected-(X1-CR-Pad5)") (class "Default")
      (node (ref "X1") (pin "5") (pinfunction "CR_5") (pintype "input"))
    )
    (net (code "110") (name "unconnected-(X1-CT-Pad2)") (class "Default")
      (node (ref "X1") (pin "2") (pinfunction "CT_2") (pintype "input"))
    )
    (net (code "111") (name "unconnected-(X1-Pad8)") (class "Default")
      (node (ref "X1") (pin "8") (pinfunction "8_8") (pintype "input"))
    )
  )
)
